# On_Board_Computer.net
KiCad netlist of a schematic drawn in EAGLE
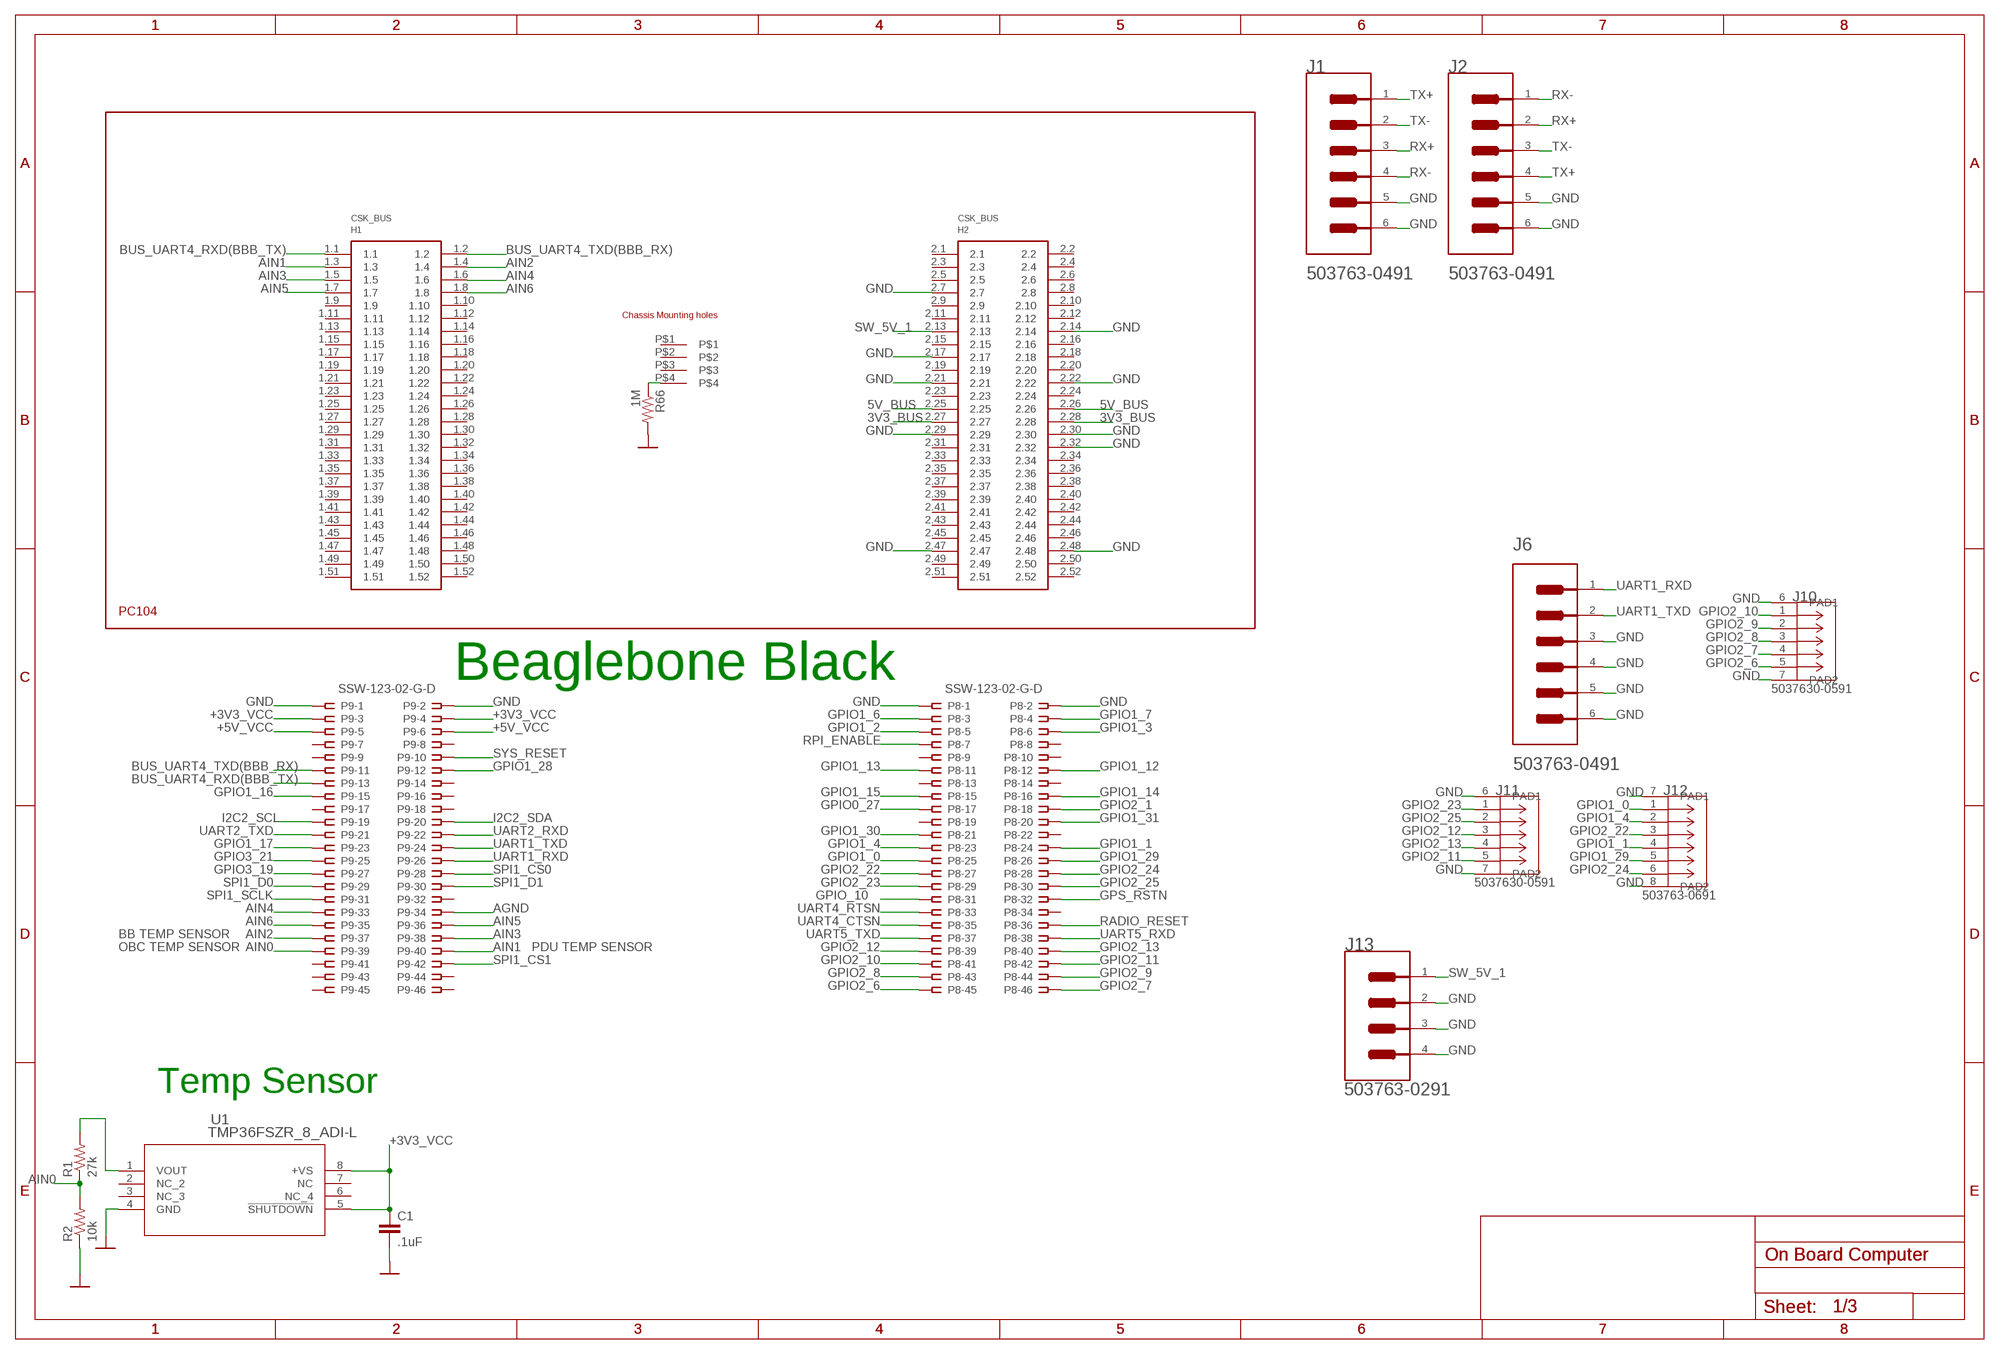
[diagram p0: schematic, sheet 1]
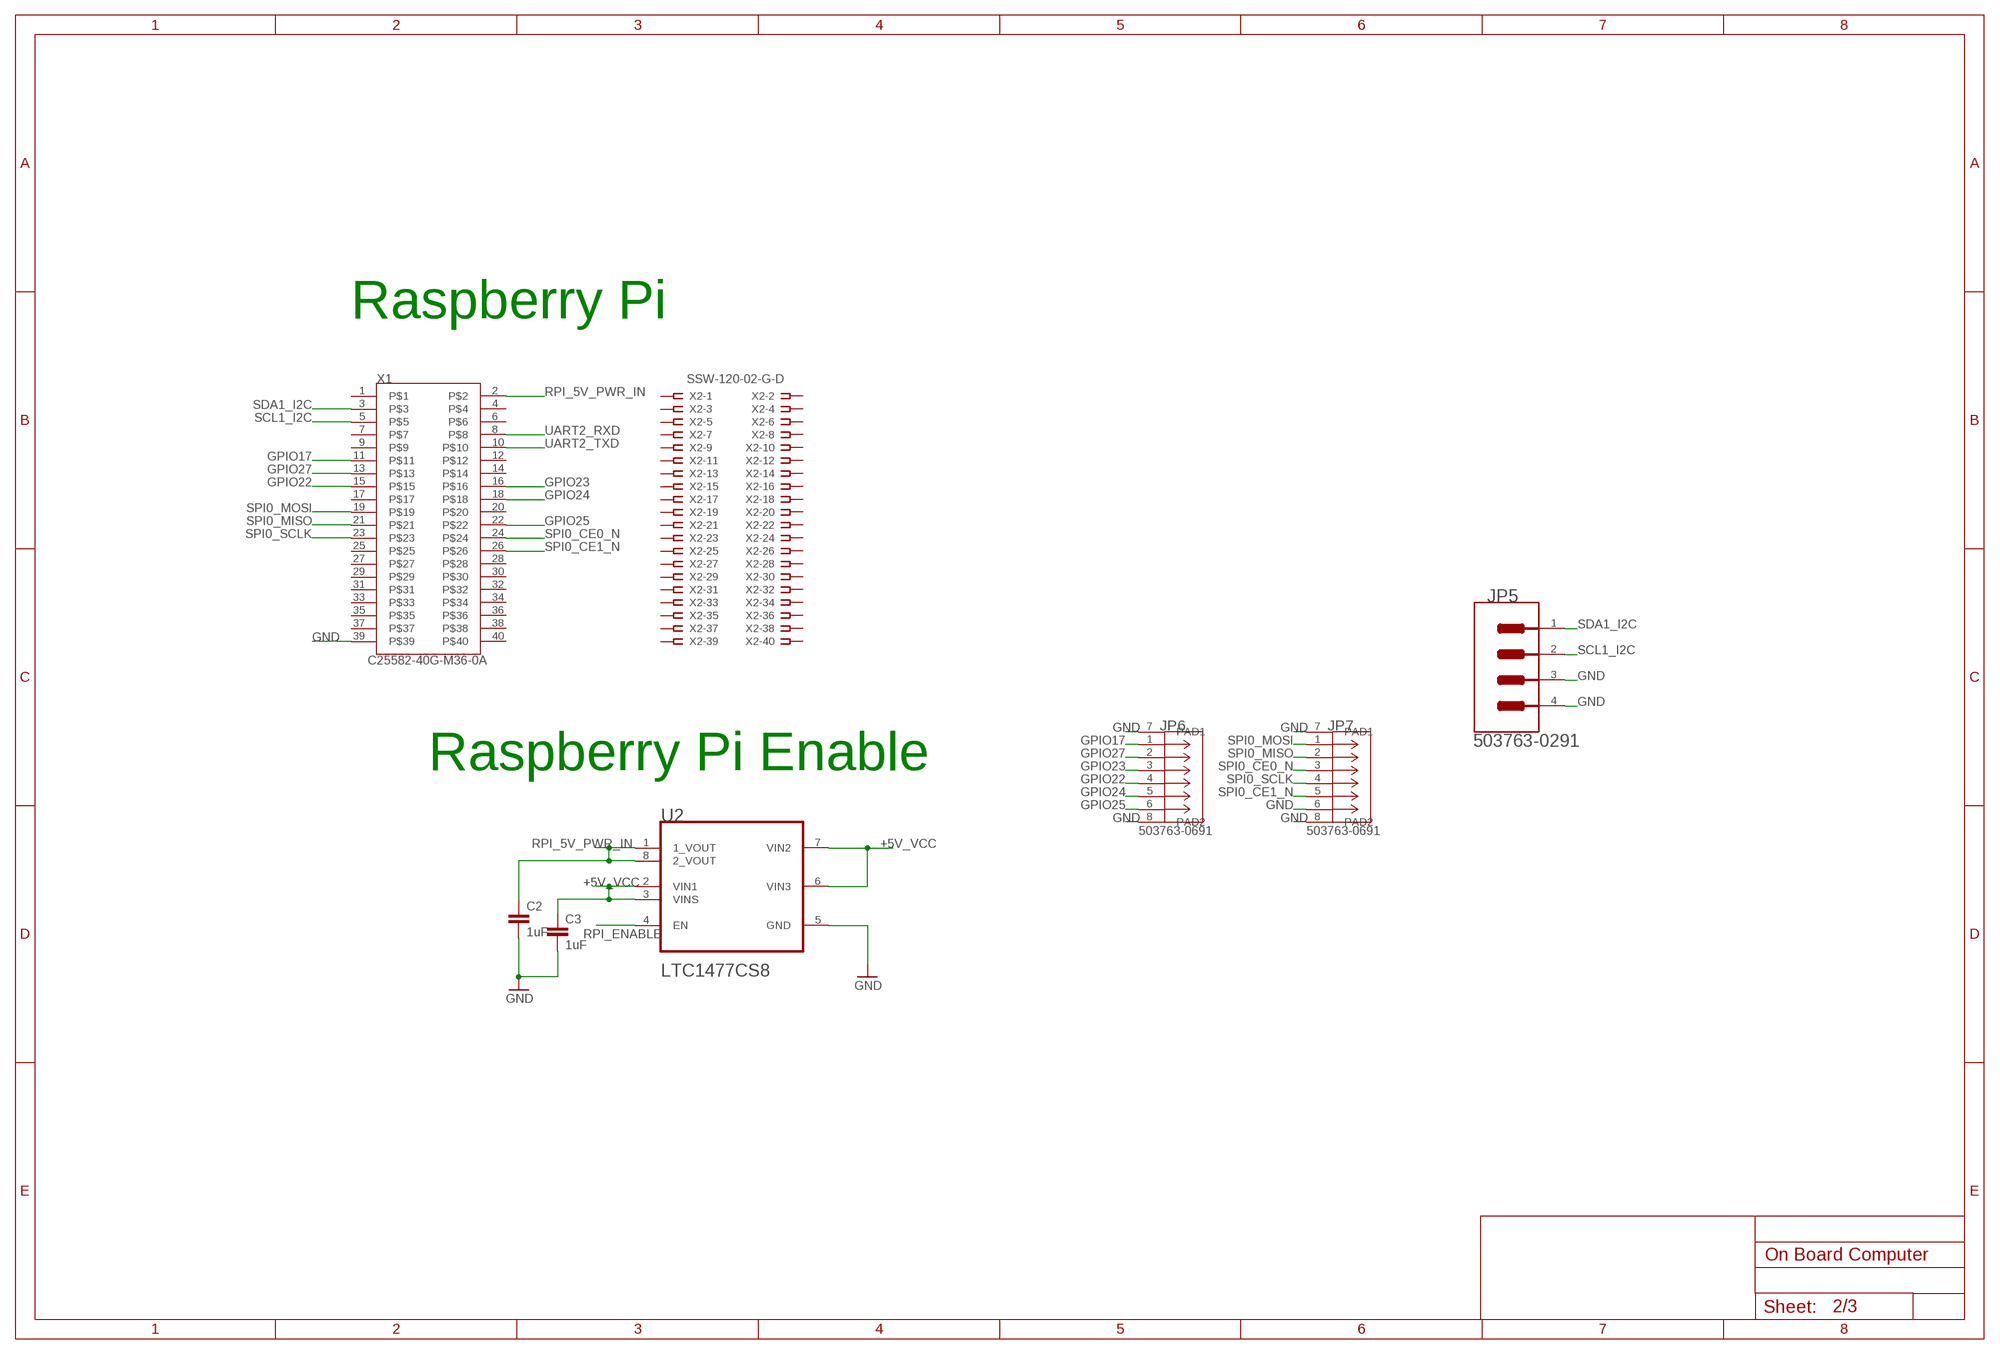
[diagram p1: schematic, sheet 2]
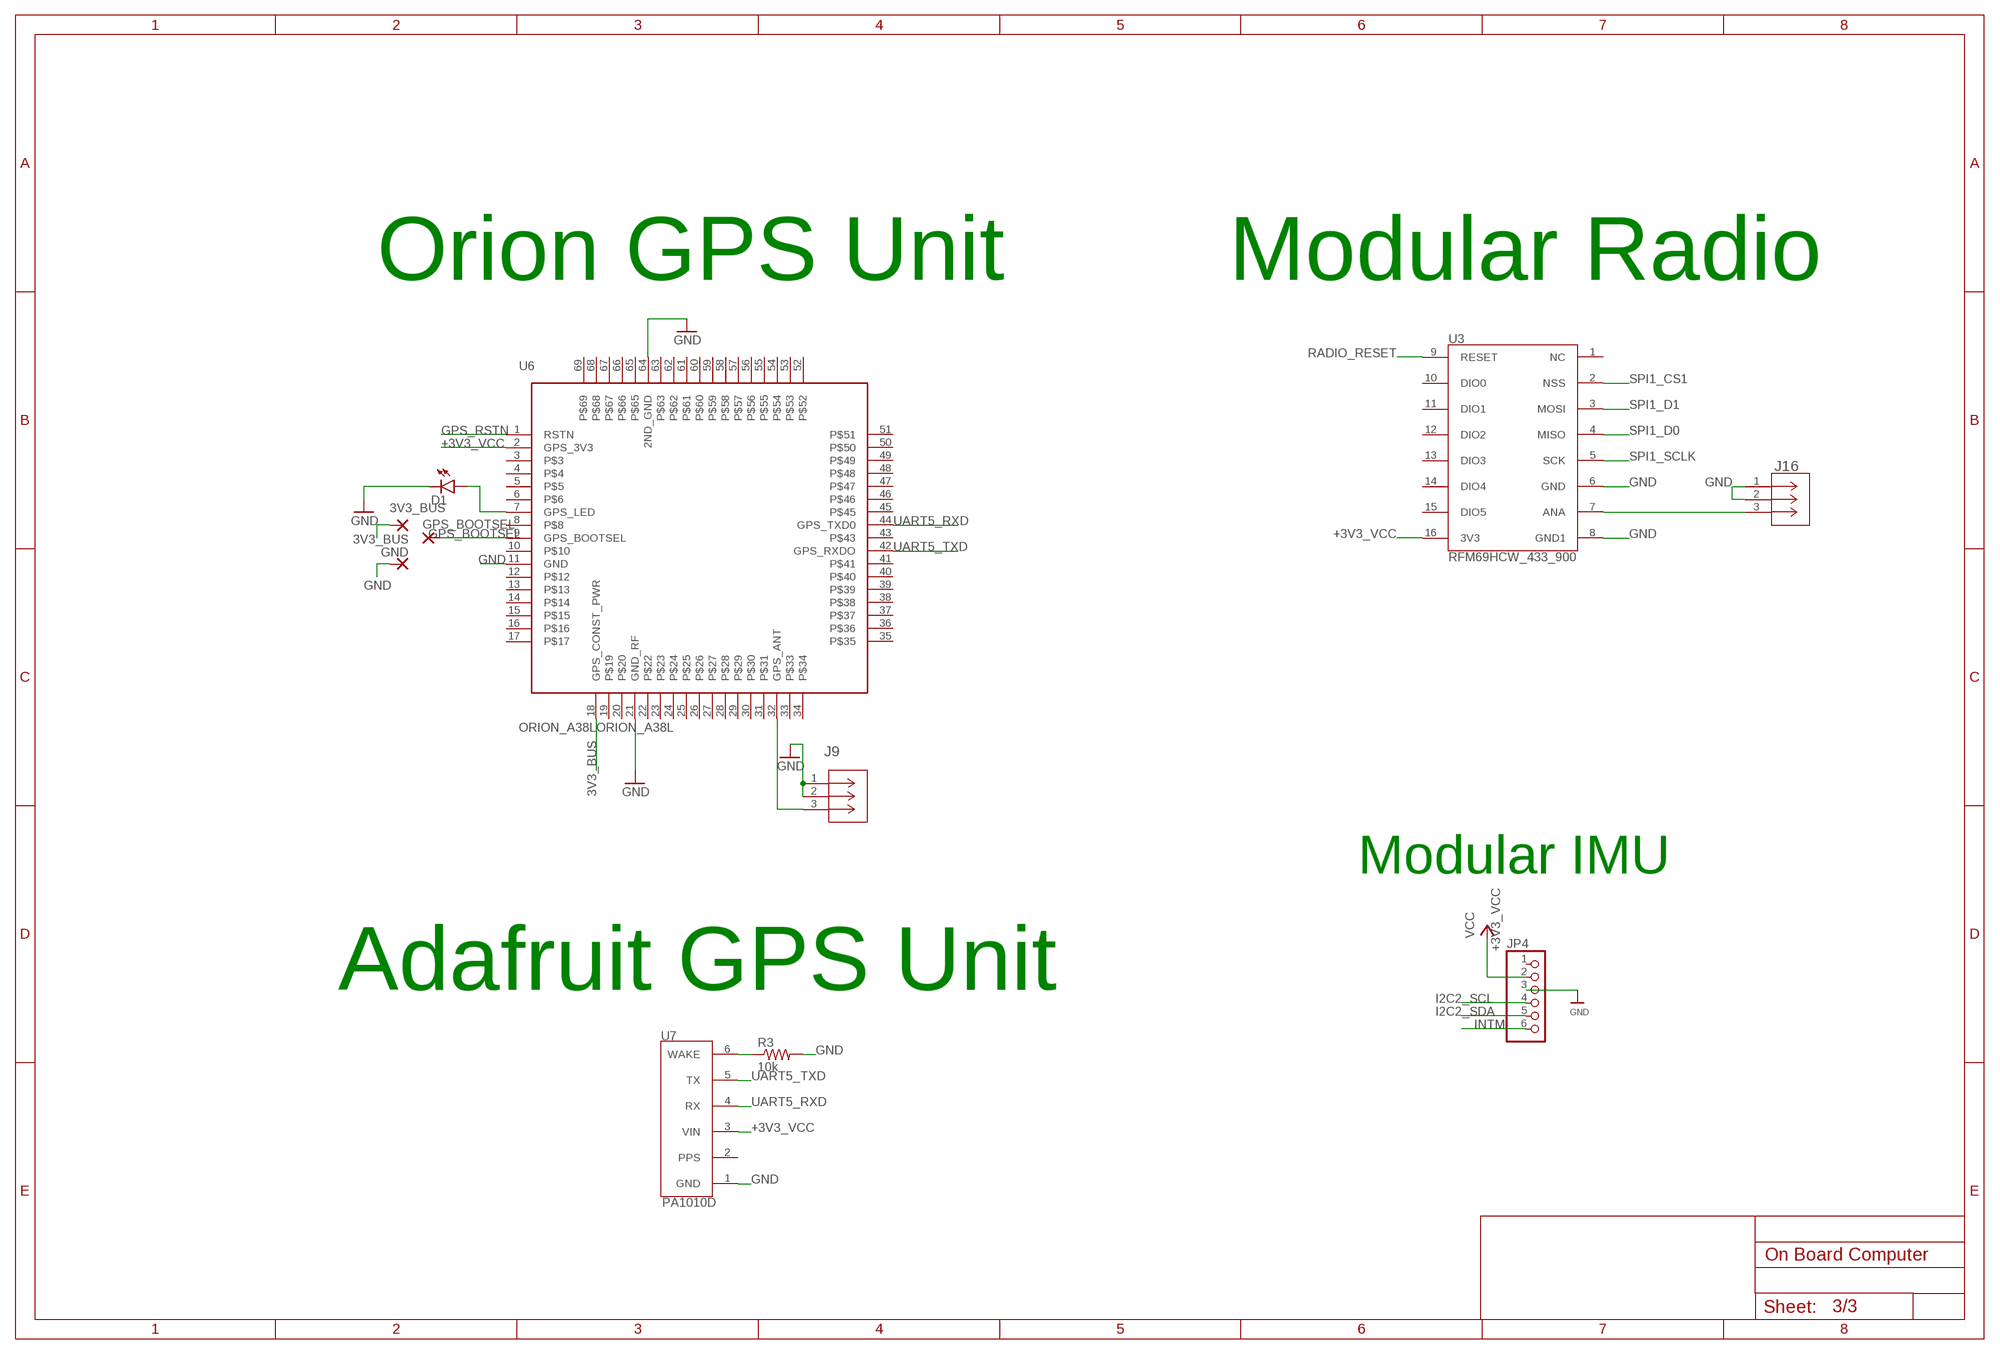
[diagram p2: schematic, sheet 3]

(export (version "E")
  (design (tool "Eeschema 10.0.6"))
  (components
    (comp (ref "3V3_BUS")
      (value "1,6/0,9")
      (footprint "eagle-import:1,6_0,9")
      (libsource (lib "eagle-import") (part "1,6/0,9"))
    )
    (comp (ref "D1")
      (value "LEDCHIP-LED0603")
      (footprint "eagle-import:CHIP-LED0603")
      (libsource (lib "eagle-import") (part "LEDCHIP-LED0603"))
    )
    (comp (ref "GND")
      (value "GND")
      (footprint "eagle-import:1,6_0,9")
      (libsource (lib "eagle-import") (part "1,6/0,9"))
    )
    (comp (ref "GPS_BOOTSEL")
      (value "1,6/0,9")
      (footprint "eagle-import:1,6_0,9")
      (libsource (lib "eagle-import") (part "1,6/0,9"))
    )
    (comp (ref "J9")
      (value "U.FL-R-SMT-1(01)")
      (footprint "eagle-import:CONN_-SMT-1(01)")
      (fields (field (name "COPYRIGHT") "Copyright (C) 2018 Accelerated Designs. All rights reserved"))
      (libsource (lib "eagle-import") (part "U.FL-R-SMT-1(01)"))
    )
    (comp (ref "J16")
      (value "U.FL-R-SMT-1(01)")
      (footprint "eagle-import:CONN_-SMT-1(01)")
      (fields (field (name "COPYRIGHT") "Copyright (C) 2018 Accelerated Designs. All rights reserved"))
      (libsource (lib "eagle-import") (part "U.FL-R-SMT-1(01)"))
    )
    (comp (ref "JP4")
      (value "HEADER-1X670MIL")
      (footprint "eagle-import:1X06_ROUND_70")
      (libsource (lib "eagle-import") (part "HEADER-1X670MIL"))
    )
    (comp (ref "R3")
      (value "10k")
      (footprint "eagle-import:0805")
      (libsource (lib "eagle-import") (part "RESISTOR0805-RES"))
    )
    (comp (ref "U3")
      (value "RFM69HCW_433_900")
      (footprint "eagle-import:RFM69HCW_433")
      (libsource (lib "eagle-import") (part "RFM69HCW_433_900"))
    )
    (comp (ref "U6")
      (value "ORION_A38LORION_A38L")
      (footprint "eagle-import:ORION_A38L")
      (libsource (lib "eagle-import") (part "ORION_A38LORION_A38L"))
    )
    (comp (ref "U7")
      (value "PA1010D")
      (footprint "eagle-import:PA1010D")
      (libsource (lib "eagle-import") (part "PA1010D"))
    )
    (comp (ref "C1")
      (value ".1uF")
      (footprint "eagle-import:0805")
      (libsource (lib "eagle-import") (part "CAP0805"))
    )
    (comp (ref "H1")
      (value "PC104_WCONN")
      (footprint "eagle-import:PC104_WCONN")
      (libsource (lib "eagle-import") (part "PC104_WCONN"))
    )
    (comp (ref "J1")
      (value "MOLEX_503763-0491MOLEX_503763-0491_0_0")
      (footprint "eagle-import:MOLEX_503763-0491_0")
      (fields
        (field (name "DIGIKEY_PART_NUMBER") "WM10655CT-ND")
        (field (name "MF") "Molex")
        (field (name "MOUSER_PART_NUMBER") "538-503763-0491")
      )
      (libsource (lib "eagle-import") (part "MOLEX_503763-0491MOLEX_503763-0491_0_0"))
    )
    (comp (ref "J2")
      (value "MOLEX_503763-0491MOLEX_503763-0491_0_0")
      (footprint "eagle-import:MOLEX_503763-0491_0")
      (fields
        (field (name "DIGIKEY_PART_NUMBER") "WM10655CT-ND")
        (field (name "MF") "Molex")
        (field (name "MOUSER_PART_NUMBER") "538-503763-0491")
      )
      (libsource (lib "eagle-import") (part "MOLEX_503763-0491MOLEX_503763-0491_0_0"))
    )
    (comp (ref "J6")
      (value "MOLEX_503763-0491MOLEX_503763-0491_0_0")
      (footprint "eagle-import:MOLEX_503763-0491_0")
      (fields
        (field (name "DIGIKEY_PART_NUMBER") "WM10655CT-ND")
        (field (name "MF") "Molex")
        (field (name "MOUSER_PART_NUMBER") "538-503763-0491")
      )
      (libsource (lib "eagle-import") (part "MOLEX_503763-0491MOLEX_503763-0491_0_0"))
    )
    (comp (ref "J10")
      (value "503763-0591")
      (footprint "eagle-import:CONN_5037630591_MOL")
      (fields (field (name "COPYRIGHT") "Copyright (C) 2018 Accelerated Designs. All rights reserved"))
      (libsource (lib "eagle-import") (part "503763-0591"))
    )
    (comp (ref "J11")
      (value "503763-0591")
      (footprint "eagle-import:CONN_5037630591_MOL")
      (fields (field (name "COPYRIGHT") "Copyright (C) 2018 Accelerated Designs. All rights reserved"))
      (libsource (lib "eagle-import") (part "503763-0591"))
    )
    (comp (ref "J12")
      (value "503763-0691")
      (footprint "eagle-import:CONN_503763-0691_MOL")
      (fields (field (name "COPYRIGHT") "Copyright (C) 2018 Accelerated Designs. All rights reserved"))
      (libsource (lib "eagle-import") (part "503763-0691"))
    )
    (comp (ref "J13")
      (value "MOLEX_503763-0291MOLEX_503763-0291_0_0")
      (footprint "eagle-import:MOLEX_503763-0291_0")
      (fields
        (field (name "DIGIKEY_PART_NUMBER") "WM10654CT-ND")
        (field (name "MF") "Molex")
        (field (name "MOUSER_PART_NUMBER") "538-503763-0291")
      )
      (libsource (lib "eagle-import") (part "MOLEX_503763-0291MOLEX_503763-0291_0_0"))
    )
    (comp (ref "P8")
      (value "SSW-123-02-G-D")
      (footprint "eagle-import:SSW-123-02-G-D")
      (fields (field (name "MF") "Samtec Inc."))
      (libsource (lib "eagle-import") (part "SSW-123-02-G-D"))
    )
    (comp (ref "P9")
      (value "SSW-123-02-G-D")
      (footprint "eagle-import:SSW-123-02-G-D")
      (fields (field (name "MF") "Samtec Inc."))
      (libsource (lib "eagle-import") (part "SSW-123-02-G-D"))
    )
    (comp (ref "R1")
      (value "27k")
      (footprint "eagle-import:0805")
      (libsource (lib "eagle-import") (part "RESISTOR0805-RES"))
    )
    (comp (ref "R2")
      (value "10k")
      (footprint "eagle-import:0805")
      (libsource (lib "eagle-import") (part "RESISTOR0805-RES"))
    )
    (comp (ref "R66")
      (value "1M")
      (footprint "eagle-import:0805")
      (libsource (lib "eagle-import") (part "RESISTOR0805-RES"))
    )
    (comp (ref "U1")
      (value "TMP36FSZR_8_ADI-L")
      (footprint "eagle-import:R_8_ADI-L")
      (fields
        (field (name "MANUFACTURER_PART_NUMBER") "TMP36FSZ")
        (field (name "COPYRIGHT") "Copyright (C) 2021 Ultra Librarian. All rights reserved.")
      )
      (libsource (lib "eagle-import") (part "TMP36FSZR_8_ADI-L"))
    )
    (comp (ref "C2")
      (value "1uF")
      (footprint "eagle-import:0805")
      (libsource (lib "eagle-import") (part "CAP0805"))
    )
    (comp (ref "C3")
      (value "1uF")
      (footprint "eagle-import:0805")
      (libsource (lib "eagle-import") (part "CAP0805"))
    )
    (comp (ref "JP5")
      (value "MOLEX_503763-0291MOLEX_503763-0291_0_0")
      (footprint "eagle-import:MOLEX_503763-0291_0")
      (fields
        (field (name "DIGIKEY_PART_NUMBER") "WM10654CT-ND")
        (field (name "MF") "Molex")
        (field (name "MOUSER_PART_NUMBER") "538-503763-0291")
      )
      (libsource (lib "eagle-import") (part "MOLEX_503763-0291MOLEX_503763-0291_0_0"))
    )
    (comp (ref "JP6")
      (value "503763-0691")
      (footprint "eagle-import:CONN_503763-0691_MOL")
      (fields (field (name "COPYRIGHT") "Copyright (C) 2018 Accelerated Designs. All rights reserved"))
      (libsource (lib "eagle-import") (part "503763-0691"))
    )
    (comp (ref "JP7")
      (value "503763-0691")
      (footprint "eagle-import:CONN_503763-0691_MOL")
      (fields (field (name "COPYRIGHT") "Copyright (C) 2018 Accelerated Designs. All rights reserved"))
      (libsource (lib "eagle-import") (part "503763-0691"))
    )
    (comp (ref "U2")
      (value "LTC1477CS8LINEAR_TECHNOLOGY_LTC1477CS8_0_2")
      (footprint "eagle-import:LINEAR_TECHNOLOGY_LTC1477CS8_2")
      (fields (field (name "MF") "Linear Technology") (field (name "MPN") "LTC1477CS8"))
      (libsource (lib "eagle-import") (part "LTC1477CS8LINEAR_TECHNOLOGY_LTC1477CS8_0_2"))
    )
    (comp (ref "X1")
      (value "C25582-40G-M36-0A")
      (footprint "eagle-import:ADAFRUIT_C25582-40G-M36-0A_0")
      (libsource (lib "eagle-import") (part "C25582-40G-M36-0A"))
    )
    (comp (ref "X2")
      (value "SSW-120-02-G-D")
      (footprint "eagle-import:SSW-120-02-G-D")
      (fields (field (name "MF") "Samtec Inc."))
      (libsource (lib "eagle-import") (part "SSW-120-02-G-D"))
    )
  )
  (nets
    (net (code "1") (name "+3V3_VCC") (class "Default")
      (node (ref "C1") (pin "1") (pinfunction "1_1") (pintype "passive"))
      (node (ref "JP4") (pin "2") (pinfunction "2_2") (pintype "passive"))
      (node (ref "P9") (pin "3") (pinfunction "1_3") (pintype "passive"))
      (node (ref "P9") (pin "4") (pinfunction "1_4") (pintype "passive"))
      (node (ref "U1") (pin "5") (pinfunction "~{SHUTDOWN}_5") (pintype "passive"))
      (node (ref "U1") (pin "8") (pinfunction "+VS_8") (pintype "power_in"))
      (node (ref "U3") (pin "16") (pinfunction "3V3_16") (pintype "bidirectional"))
      (node (ref "U6") (pin "2") (pinfunction "GPS_3V3_2") (pintype "bidirectional"))
      (node (ref "U7") (pin "3") (pinfunction "VIN_3") (pintype "bidirectional"))
    )
    (net (code "2") (name "+5V_VCC") (class "Default")
      (node (ref "C3") (pin "1") (pinfunction "1_1") (pintype "passive"))
      (node (ref "P9") (pin "5") (pinfunction "1_5") (pintype "passive"))
      (node (ref "P9") (pin "6") (pinfunction "1_6") (pintype "passive"))
      (node (ref "U2") (pin "2") (pinfunction "VIN1_2") (pintype "power_in"))
      (node (ref "U2") (pin "3") (pinfunction "VINS_3") (pintype "power_in"))
      (node (ref "U2") (pin "6") (pinfunction "VIN3_6") (pintype "power_in"))
      (node (ref "U2") (pin "7") (pinfunction "VIN2_7") (pintype "power_in"))
    )
    (net (code "3") (name "3V3_BUS") (class "Default")
      (node (ref "3V3_BUS") (pin "1") (pinfunction "P_1") (pintype "passive"))
      (node (ref "H1") (pin "2.27") (pinfunction "2.27_2.27") (pintype "bidirectional"))
      (node (ref "H1") (pin "2.28") (pinfunction "2.28_2.28") (pintype "bidirectional"))
      (node (ref "U6") (pin "18") (pinfunction "GPS_CONST_PWR_18") (pintype "bidirectional"))
    )
    (net (code "4") (name "5V_BUS") (class "Default")
      (node (ref "H1") (pin "2.25") (pinfunction "2.25_2.25") (pintype "bidirectional"))
      (node (ref "H1") (pin "2.26") (pinfunction "2.26_2.26") (pintype "bidirectional"))
    )
    (net (code "5") (name "AGND") (class "Default")
      (node (ref "P9") (pin "34") (pinfunction "1_34") (pintype "passive"))
    )
    (net (code "6") (name "AIN0") (class "Default")
      (node (ref "P9") (pin "39") (pinfunction "1_39") (pintype "passive"))
      (node (ref "R1") (pin "1") (pinfunction "1_1") (pintype "passive"))
      (node (ref "R2") (pin "2") (pinfunction "2_2") (pintype "passive"))
    )
    (net (code "7") (name "AIN1") (class "Default")
      (node (ref "H1") (pin "1.3") (pinfunction "1.3_1.3") (pintype "bidirectional"))
      (node (ref "P9") (pin "40") (pinfunction "1_40") (pintype "passive"))
    )
    (net (code "8") (name "AIN2") (class "Default")
      (node (ref "H1") (pin "1.4") (pinfunction "1.4_1.4") (pintype "bidirectional"))
      (node (ref "P9") (pin "37") (pinfunction "1_37") (pintype "passive"))
    )
    (net (code "9") (name "AIN3") (class "Default")
      (node (ref "H1") (pin "1.5") (pinfunction "1.5_1.5") (pintype "bidirectional"))
      (node (ref "P9") (pin "38") (pinfunction "1_38") (pintype "passive"))
    )
    (net (code "10") (name "AIN4") (class "Default")
      (node (ref "H1") (pin "1.6") (pinfunction "1.6_1.6") (pintype "bidirectional"))
      (node (ref "P9") (pin "33") (pinfunction "1_33") (pintype "passive"))
    )
    (net (code "11") (name "AIN5") (class "Default")
      (node (ref "H1") (pin "1.7") (pinfunction "1.7_1.7") (pintype "bidirectional"))
      (node (ref "P9") (pin "36") (pinfunction "1_36") (pintype "passive"))
    )
    (net (code "12") (name "AIN6") (class "Default")
      (node (ref "H1") (pin "1.8") (pinfunction "1.8_1.8") (pintype "bidirectional"))
      (node (ref "P9") (pin "35") (pinfunction "1_35") (pintype "passive"))
    )
    (net (code "13") (name "BUS_UART4_RXD(BBB_TX)") (class "Default")
      (node (ref "H1") (pin "1.1") (pinfunction "1.1_1.1") (pintype "bidirectional"))
      (node (ref "P9") (pin "13") (pinfunction "1_13") (pintype "passive"))
    )
    (net (code "14") (name "BUS_UART4_TXD(BBB_RX)") (class "Default")
      (node (ref "H1") (pin "1.2") (pinfunction "1.2_1.2") (pintype "bidirectional"))
      (node (ref "P9") (pin "11") (pinfunction "1_11") (pintype "passive"))
    )
    (net (code "15") (name "GND") (class "Default")
      (node (ref "C1") (pin "2") (pinfunction "2_2") (pintype "passive"))
      (node (ref "C2") (pin "2") (pinfunction "2_2") (pintype "passive"))
      (node (ref "C3") (pin "2") (pinfunction "2_2") (pintype "passive"))
      (node (ref "D1") (pin "C") (pinfunction "C_C") (pintype "passive"))
      (node (ref "GND") (pin "1") (pinfunction "P_1") (pintype "passive"))
      (node (ref "H1") (pin "2.14") (pinfunction "2.14_2.14") (pintype "bidirectional"))
      (node (ref "H1") (pin "2.17") (pinfunction "2.17_2.17") (pintype "bidirectional"))
      (node (ref "H1") (pin "2.21") (pinfunction "2.21_2.21") (pintype "bidirectional"))
      (node (ref "H1") (pin "2.22") (pinfunction "2.22_2.22") (pintype "bidirectional"))
      (node (ref "H1") (pin "2.29") (pinfunction "2.29_2.29") (pintype "bidirectional"))
      (node (ref "H1") (pin "2.30") (pinfunction "2.30_2.30") (pintype "bidirectional"))
      (node (ref "H1") (pin "2.32") (pinfunction "2.32_2.32") (pintype "bidirectional"))
      (node (ref "H1") (pin "2.47") (pinfunction "2.47_2.47") (pintype "bidirectional"))
      (node (ref "H1") (pin "2.48") (pinfunction "2.48_2.48") (pintype "bidirectional"))
      (node (ref "H1") (pin "2.7") (pinfunction "2.7_2.7") (pintype "bidirectional"))
      (node (ref "J1") (pin "5") (pinfunction "MNT_1_5") (pintype "passive"))
      (node (ref "J1") (pin "6") (pinfunction "MNT_2_6") (pintype "passive"))
      (node (ref "J10") (pin "6") (pinfunction "PAD1_6") (pintype "bidirectional"))
      (node (ref "J10") (pin "7") (pinfunction "PAD2_7") (pintype "bidirectional"))
      (node (ref "J11") (pin "6") (pinfunction "PAD1_6") (pintype "bidirectional"))
      (node (ref "J11") (pin "7") (pinfunction "PAD2_7") (pintype "bidirectional"))
      (node (ref "J12") (pin "7") (pinfunction "PAD1_7") (pintype "bidirectional"))
      (node (ref "J12") (pin "8") (pinfunction "PAD2_8") (pintype "bidirectional"))
      (node (ref "J13") (pin "2") (pinfunction "2_2") (pintype "bidirectional"))
      (node (ref "J13") (pin "3") (pinfunction "MNT_1_3") (pintype "bidirectional"))
      (node (ref "J13") (pin "4") (pinfunction "MNT_2_4") (pintype "bidirectional"))
      (node (ref "J16") (pin "1") (pinfunction "1_1") (pintype "passive"))
      (node (ref "J16") (pin "2") (pinfunction "2_2") (pintype "passive"))
      (node (ref "J2") (pin "5") (pinfunction "MNT_1_5") (pintype "passive"))
      (node (ref "J2") (pin "6") (pinfunction "MNT_2_6") (pintype "passive"))
      (node (ref "J6") (pin "3") (pinfunction "3_3") (pintype "passive"))
      (node (ref "J6") (pin "4") (pinfunction "4_4") (pintype "passive"))
      (node (ref "J6") (pin "5") (pinfunction "MNT_1_5") (pintype "passive"))
      (node (ref "J6") (pin "6") (pinfunction "MNT_2_6") (pintype "passive"))
      (node (ref "J9") (pin "1") (pinfunction "1_1") (pintype "passive"))
      (node (ref "J9") (pin "2") (pinfunction "2_2") (pintype "passive"))
      (node (ref "JP4") (pin "3") (pinfunction "3_3") (pintype "passive"))
      (node (ref "JP5") (pin "3") (pinfunction "MNT_1_3") (pintype "bidirectional"))
      (node (ref "JP5") (pin "4") (pinfunction "MNT_2_4") (pintype "bidirectional"))
      (node (ref "JP6") (pin "7") (pinfunction "PAD1_7") (pintype "bidirectional"))
      (node (ref "JP6") (pin "8") (pinfunction "PAD2_8") (pintype "bidirectional"))
      (node (ref "JP7") (pin "6") (pinfunction "6_6") (pintype "passive"))
      (node (ref "JP7") (pin "7") (pinfunction "PAD1_7") (pintype "bidirectional"))
      (node (ref "JP7") (pin "8") (pinfunction "PAD2_8") (pintype "bidirectional"))
      (node (ref "P8") (pin "1") (pinfunction "1_1") (pintype "passive"))
      (node (ref "P8") (pin "2") (pinfunction "1_2") (pintype "passive"))
      (node (ref "P9") (pin "1") (pinfunction "1_1") (pintype "passive"))
      (node (ref "P9") (pin "2") (pinfunction "1_2") (pintype "passive"))
      (node (ref "R2") (pin "1") (pinfunction "1_1") (pintype "passive"))
      (node (ref "R3") (pin "2") (pinfunction "2_2") (pintype "passive"))
      (node (ref "R66") (pin "2") (pinfunction "2_2") (pintype "passive"))
      (node (ref "U1") (pin "4") (pinfunction "GND_4") (pintype "passive"))
      (node (ref "U2") (pin "5") (pinfunction "GND_5") (pintype "power_in"))
      (node (ref "U3") (pin "6") (pinfunction "GND_6") (pintype "bidirectional"))
      (node (ref "U3") (pin "8") (pinfunction "GND1_8") (pintype "bidirectional"))
      (node (ref "U6") (pin "11") (pinfunction "GND_11") (pintype "bidirectional"))
      (node (ref "U6") (pin "21") (pinfunction "GND_RF_21") (pintype "bidirectional"))
      (node (ref "U6") (pin "64") (pinfunction "2ND_GND_64") (pintype "bidirectional"))
      (node (ref "U7") (pin "1") (pinfunction "GND_1") (pintype "bidirectional"))
      (node (ref "X1") (pin "39") (pinfunction "P$39_39") (pintype "bidirectional"))
    )
    (net (code "16") (name "GPIO0_27") (class "Default")
      (node (ref "P8") (pin "17") (pinfunction "1_17") (pintype "passive"))
    )
    (net (code "17") (name "GPIO1_0") (class "Default")
      (node (ref "J12") (pin "1") (pinfunction "1_1") (pintype "passive"))
      (node (ref "P8") (pin "25") (pinfunction "1_25") (pintype "passive"))
    )
    (net (code "18") (name "GPIO1_1") (class "Default")
      (node (ref "J12") (pin "4") (pinfunction "4_4") (pintype "passive"))
      (node (ref "P8") (pin "24") (pinfunction "1_24") (pintype "passive"))
    )
    (net (code "19") (name "GPIO1_2") (class "Default")
      (node (ref "P8") (pin "5") (pinfunction "1_5") (pintype "passive"))
    )
    (net (code "20") (name "GPIO1_3") (class "Default")
      (node (ref "P8") (pin "6") (pinfunction "1_6") (pintype "passive"))
    )
    (net (code "21") (name "GPIO1_4") (class "Default")
      (node (ref "J12") (pin "2") (pinfunction "2_2") (pintype "passive"))
      (node (ref "P8") (pin "23") (pinfunction "1_23") (pintype "passive"))
    )
    (net (code "22") (name "GPIO1_6") (class "Default")
      (node (ref "P8") (pin "3") (pinfunction "1_3") (pintype "passive"))
    )
    (net (code "23") (name "GPIO1_7") (class "Default")
      (node (ref "P8") (pin "4") (pinfunction "1_4") (pintype "passive"))
    )
    (net (code "24") (name "GPIO1_12") (class "Default")
      (node (ref "P8") (pin "12") (pinfunction "1_12") (pintype "passive"))
    )
    (net (code "25") (name "GPIO1_13") (class "Default")
      (node (ref "P8") (pin "11") (pinfunction "1_11") (pintype "passive"))
    )
    (net (code "26") (name "GPIO1_14") (class "Default")
      (node (ref "P8") (pin "16") (pinfunction "1_16") (pintype "passive"))
    )
    (net (code "27") (name "GPIO1_15") (class "Default")
      (node (ref "P8") (pin "15") (pinfunction "1_15") (pintype "passive"))
    )
    (net (code "28") (name "GPIO1_16") (class "Default")
      (node (ref "P9") (pin "15") (pinfunction "1_15") (pintype "passive"))
    )
    (net (code "29") (name "GPIO1_17") (class "Default")
      (node (ref "P9") (pin "23") (pinfunction "1_23") (pintype "passive"))
    )
    (net (code "30") (name "GPIO1_28") (class "Default")
      (node (ref "P9") (pin "12") (pinfunction "1_12") (pintype "passive"))
    )
    (net (code "31") (name "GPIO1_29") (class "Default")
      (node (ref "J12") (pin "5") (pinfunction "5_5") (pintype "passive"))
      (node (ref "P8") (pin "26") (pinfunction "1_26") (pintype "passive"))
    )
    (net (code "32") (name "GPIO1_30") (class "Default")
      (node (ref "P8") (pin "21") (pinfunction "1_21") (pintype "passive"))
    )
    (net (code "33") (name "GPIO1_31") (class "Default")
      (node (ref "P8") (pin "20") (pinfunction "1_20") (pintype "passive"))
    )
    (net (code "34") (name "GPIO2_1") (class "Default")
      (node (ref "P8") (pin "18") (pinfunction "1_18") (pintype "passive"))
    )
    (net (code "35") (name "GPIO2_6") (class "Default")
      (node (ref "J10") (pin "5") (pinfunction "5_5") (pintype "passive"))
      (node (ref "P8") (pin "45") (pinfunction "1_45") (pintype "passive"))
    )
    (net (code "36") (name "GPIO2_7") (class "Default")
      (node (ref "J10") (pin "4") (pinfunction "4_4") (pintype "passive"))
      (node (ref "P8") (pin "46") (pinfunction "1_46") (pintype "passive"))
    )
    (net (code "37") (name "GPIO2_8") (class "Default")
      (node (ref "J10") (pin "3") (pinfunction "3_3") (pintype "passive"))
      (node (ref "P8") (pin "43") (pinfunction "1_43") (pintype "passive"))
    )
    (net (code "38") (name "GPIO2_9") (class "Default")
      (node (ref "J10") (pin "2") (pinfunction "2_2") (pintype "passive"))
      (node (ref "P8") (pin "44") (pinfunction "1_44") (pintype "passive"))
    )
    (net (code "39") (name "GPIO2_10") (class "Default")
      (node (ref "J10") (pin "1") (pinfunction "1_1") (pintype "passive"))
      (node (ref "P8") (pin "41") (pinfunction "1_41") (pintype "passive"))
    )
    (net (code "40") (name "GPIO2_11") (class "Default")
      (node (ref "J11") (pin "5") (pinfunction "5_5") (pintype "passive"))
      (node (ref "P8") (pin "42") (pinfunction "1_42") (pintype "passive"))
    )
    (net (code "41") (name "GPIO2_12") (class "Default")
      (node (ref "J11") (pin "3") (pinfunction "3_3") (pintype "passive"))
      (node (ref "P8") (pin "39") (pinfunction "1_39") (pintype "passive"))
    )
    (net (code "42") (name "GPIO2_13") (class "Default")
      (node (ref "J11") (pin "4") (pinfunction "4_4") (pintype "passive"))
      (node (ref "P8") (pin "40") (pinfunction "1_40") (pintype "passive"))
    )
    (net (code "43") (name "GPIO2_22") (class "Default")
      (node (ref "J12") (pin "3") (pinfunction "3_3") (pintype "passive"))
      (node (ref "P8") (pin "27") (pinfunction "1_27") (pintype "passive"))
    )
    (net (code "44") (name "GPIO2_23") (class "Default")
      (node (ref "J11") (pin "1") (pinfunction "1_1") (pintype "passive"))
      (node (ref "P8") (pin "29") (pinfunction "1_29") (pintype "passive"))
    )
    (net (code "45") (name "GPIO2_24") (class "Default")
      (node (ref "J12") (pin "6") (pinfunction "6_6") (pintype "passive"))
      (node (ref "P8") (pin "28") (pinfunction "1_28") (pintype "passive"))
    )
    (net (code "46") (name "GPIO2_25") (class "Default")
      (node (ref "J11") (pin "2") (pinfunction "2_2") (pintype "passive"))
      (node (ref "P8") (pin "30") (pinfunction "1_30") (pintype "passive"))
    )
    (net (code "47") (name "GPIO3_19") (class "Default")
      (node (ref "P9") (pin "27") (pinfunction "1_27") (pintype "passive"))
    )
    (net (code "48") (name "GPIO3_21") (class "Default")
      (node (ref "P9") (pin "25") (pinfunction "1_25") (pintype "passive"))
    )
    (net (code "49") (name "GPIO17") (class "Default")
      (node (ref "JP6") (pin "1") (pinfunction "1_1") (pintype "passive"))
      (node (ref "X1") (pin "11") (pinfunction "P$11_11") (pintype "bidirectional"))
    )
    (net (code "50") (name "GPIO22") (class "Default")
      (node (ref "JP6") (pin "4") (pinfunction "4_4") (pintype "passive"))
      (node (ref "X1") (pin "15") (pinfunction "P$15_15") (pintype "bidirectional"))
    )
    (net (code "51") (name "GPIO23") (class "Default")
      (node (ref "JP6") (pin "3") (pinfunction "3_3") (pintype "passive"))
      (node (ref "X1") (pin "16") (pinfunction "P$16_16") (pintype "bidirectional"))
    )
    (net (code "52") (name "GPIO24") (class "Default")
      (node (ref "JP6") (pin "5") (pinfunction "5_5") (pintype "passive"))
      (node (ref "X1") (pin "18") (pinfunction "P$18_18") (pintype "bidirectional"))
    )
    (net (code "53") (name "GPIO25") (class "Default")
      (node (ref "JP6") (pin "6") (pinfunction "6_6") (pintype "passive"))
      (node (ref "X1") (pin "22") (pinfunction "P$22_22") (pintype "bidirectional"))
    )
    (net (code "54") (name "GPIO27") (class "Default")
      (node (ref "JP6") (pin "2") (pinfunction "2_2") (pintype "passive"))
      (node (ref "X1") (pin "13") (pinfunction "P$13_13") (pintype "bidirectional"))
    )
    (net (code "55") (name "GPIO_10") (class "Default")
      (node (ref "P8") (pin "31") (pinfunction "1_31") (pintype "passive"))
    )
    (net (code "56") (name "GPS_BOOTSEL") (class "Default")
      (node (ref "GPS_BOOTSEL") (pin "1") (pinfunction "P_1") (pintype "passive"))
      (node (ref "U6") (pin "9") (pinfunction "GPS_BOOTSEL_9") (pintype "bidirectional"))
    )
    (net (code "57") (name "GPS_RSTN") (class "Default")
      (node (ref "P8") (pin "32") (pinfunction "1_32") (pintype "passive"))
      (node (ref "U6") (pin "1") (pinfunction "RSTN_1") (pintype "bidirectional"))
    )
    (net (code "58") (name "I2C2_SCL") (class "Default")
      (node (ref "JP4") (pin "4") (pinfunction "4_4") (pintype "passive"))
      (node (ref "P9") (pin "19") (pinfunction "1_19") (pintype "passive"))
    )
    (net (code "59") (name "I2C2_SDA") (class "Default")
      (node (ref "JP4") (pin "5") (pinfunction "5_5") (pintype "passive"))
      (node (ref "P9") (pin "20") (pinfunction "1_20") (pintype "passive"))
    )
    (net (code "60") (name "INTM") (class "Default")
      (node (ref "JP4") (pin "6") (pinfunction "6_6") (pintype "passive"))
    )
    (net (code "61") (name "Net-(H1-PadP$4)") (class "Default")
      (node (ref "H1") (pin "P$4") (pinfunction "P$4_P$4") (pintype "bidirectional"))
      (node (ref "R66") (pin "1") (pinfunction "1_1") (pintype "passive"))
    )
    (net (code "62") (name "Net-(U1-VOUT)") (class "Default")
      (node (ref "R1") (pin "2") (pinfunction "2_2") (pintype "passive"))
      (node (ref "U1") (pin "1") (pinfunction "VOUT_1") (pintype "output"))
    )
    (net (code "63") (name "Net-(U3-ANA)") (class "Default")
      (node (ref "J16") (pin "3") (pinfunction "3_3") (pintype "passive"))
      (node (ref "U3") (pin "7") (pinfunction "ANA_7") (pintype "bidirectional"))
    )
    (net (code "64") (name "Net-(U6-GPS_ANT)") (class "Default")
      (node (ref "J9") (pin "3") (pinfunction "3_3") (pintype "passive"))
      (node (ref "U6") (pin "32") (pinfunction "GPS_ANT_32") (pintype "bidirectional"))
    )
    (net (code "65") (name "Net-(U6-GPS_LED)") (class "Default")
      (node (ref "D1") (pin "A") (pinfunction "A_A") (pintype "passive"))
      (node (ref "U6") (pin "7") (pinfunction "GPS_LED_7") (pintype "bidirectional"))
    )
    (net (code "66") (name "Net-(U7-WAKE)") (class "Default")
      (node (ref "R3") (pin "1") (pinfunction "1_1") (pintype "passive"))
      (node (ref "U7") (pin "6") (pinfunction "WAKE_6") (pintype "bidirectional"))
    )
    (net (code "67") (name "RADIO_RESET") (class "Default")
      (node (ref "P8") (pin "36") (pinfunction "1_36") (pintype "passive"))
      (node (ref "U3") (pin "9") (pinfunction "RESET_9") (pintype "bidirectional"))
    )
    (net (code "68") (name "RPI_5V_PWR_IN") (class "Default")
      (node (ref "C2") (pin "1") (pinfunction "1_1") (pintype "passive"))
      (node (ref "U2") (pin "1") (pinfunction "1_VOUT_1") (pintype "power_in"))
      (node (ref "U2") (pin "8") (pinfunction "2_VOUT_8") (pintype "power_in"))
      (node (ref "X1") (pin "2") (pinfunction "P$2_2") (pintype "bidirectional"))
    )
    (net (code "69") (name "RPI_ENABLE") (class "Default")
      (node (ref "P8") (pin "7") (pinfunction "1_7") (pintype "passive"))
      (node (ref "U2") (pin "4") (pinfunction "EN_4") (pintype "input"))
    )
    (net (code "70") (name "RX+") (class "Default")
      (node (ref "J1") (pin "3") (pinfunction "3_3") (pintype "passive"))
      (node (ref "J2") (pin "2") (pinfunction "2_2") (pintype "passive"))
    )
    (net (code "71") (name "RX-") (class "Default")
      (node (ref "J1") (pin "4") (pinfunction "4_4") (pintype "passive"))
      (node (ref "J2") (pin "1") (pinfunction "1_1") (pintype "passive"))
    )
    (net (code "72") (name "SCL1_I2C") (class "Default")
      (node (ref "JP5") (pin "2") (pinfunction "2_2") (pintype "bidirectional"))
      (node (ref "X1") (pin "5") (pinfunction "P$5_5") (pintype "bidirectional"))
    )
    (net (code "73") (name "SDA1_I2C") (class "Default")
      (node (ref "JP5") (pin "1") (pinfunction "1_1") (pintype "bidirectional"))
      (node (ref "X1") (pin "3") (pinfunction "P$3_3") (pintype "bidirectional"))
    )
    (net (code "74") (name "SPI0_CE0_N") (class "Default")
      (node (ref "JP7") (pin "3") (pinfunction "3_3") (pintype "passive"))
      (node (ref "X1") (pin "24") (pinfunction "P$24_24") (pintype "bidirectional"))
    )
    (net (code "75") (name "SPI0_CE1_N") (class "Default")
      (node (ref "JP7") (pin "5") (pinfunction "5_5") (pintype "passive"))
      (node (ref "X1") (pin "26") (pinfunction "P$26_26") (pintype "bidirectional"))
    )
    (net (code "76") (name "SPI0_MISO") (class "Default")
      (node (ref "JP7") (pin "2") (pinfunction "2_2") (pintype "passive"))
      (node (ref "X1") (pin "21") (pinfunction "P$21_21") (pintype "bidirectional"))
    )
    (net (code "77") (name "SPI0_MOSI") (class "Default")
      (node (ref "JP7") (pin "1") (pinfunction "1_1") (pintype "passive"))
      (node (ref "X1") (pin "19") (pinfunction "P$19_19") (pintype "bidirectional"))
    )
    (net (code "78") (name "SPI0_SCLK") (class "Default")
      (node (ref "JP7") (pin "4") (pinfunction "4_4") (pintype "passive"))
      (node (ref "X1") (pin "23") (pinfunction "P$23_23") (pintype "bidirectional"))
    )
    (net (code "79") (name "SPI1_CS0") (class "Default")
      (node (ref "P9") (pin "28") (pinfunction "1_28") (pintype "passive"))
    )
    (net (code "80") (name "SPI1_CS1") (class "Default")
      (node (ref "P9") (pin "42") (pinfunction "1_42") (pintype "passive"))
      (node (ref "U3") (pin "2") (pinfunction "NSS_2") (pintype "bidirectional"))
    )
    (net (code "81") (name "SPI1_D0") (class "Default")
      (node (ref "P9") (pin "29") (pinfunction "1_29") (pintype "passive"))
      (node (ref "U3") (pin "4") (pinfunction "MISO_4") (pintype "bidirectional"))
    )
    (net (code "82") (name "SPI1_D1") (class "Default")
      (node (ref "P9") (pin "30") (pinfunction "1_30") (pintype "passive"))
      (node (ref "U3") (pin "3") (pinfunction "MOSI_3") (pintype "bidirectional"))
    )
    (net (code "83") (name "SPI1_SCLK") (class "Default")
      (node (ref "P9") (pin "31") (pinfunction "1_31") (pintype "passive"))
      (node (ref "U3") (pin "5") (pinfunction "SCK_5") (pintype "bidirectional"))
    )
    (net (code "84") (name "SW_5V_1") (class "Default")
      (node (ref "H1") (pin "2.13") (pinfunction "2.13_2.13") (pintype "bidirectional"))
      (node (ref "J13") (pin "1") (pinfunction "1_1") (pintype "bidirectional"))
    )
    (net (code "85") (name "SYS_RESET") (class "Default")
      (node (ref "P9") (pin "10") (pinfunction "1_10") (pintype "passive"))
    )
    (net (code "86") (name "TX+") (class "Default")
      (node (ref "J1") (pin "1") (pinfunction "1_1") (pintype "passive"))
      (node (ref "J2") (pin "4") (pinfunction "4_4") (pintype "passive"))
    )
    (net (code "87") (name "TX-") (class "Default")
      (node (ref "J1") (pin "2") (pinfunction "2_2") (pintype "passive"))
      (node (ref "J2") (pin "3") (pinfunction "3_3") (pintype "passive"))
    )
    (net (code "88") (name "UART1_RXD") (class "Default")
      (node (ref "J6") (pin "1") (pinfunction "1_1") (pintype "passive"))
      (node (ref "P9") (pin "26") (pinfunction "1_26") (pintype "passive"))
    )
    (net (code "89") (name "UART1_TXD") (class "Default")
      (node (ref "J6") (pin "2") (pinfunction "2_2") (pintype "passive"))
      (node (ref "P9") (pin "24") (pinfunction "1_24") (pintype "passive"))
    )
    (net (code "90") (name "UART2_RXD") (class "Default")
      (node (ref "P9") (pin "22") (pinfunction "1_22") (pintype "passive"))
      (node (ref "X1") (pin "8") (pinfunction "P$8_8") (pintype "bidirectional"))
    )
    (net (code "91") (name "UART2_TXD") (class "Default")
      (node (ref "P9") (pin "21") (pinfunction "1_21") (pintype "passive"))
      (node (ref "X1") (pin "10") (pinfunction "P$10_10") (pintype "bidirectional"))
    )
    (net (code "92") (name "UART4_CTSN") (class "Default")
      (node (ref "P8") (pin "35") (pinfunction "1_35") (pintype "passive"))
    )
    (net (code "93") (name "UART4_RTSN") (class "Default")
      (node (ref "P8") (pin "33") (pinfunction "1_33") (pintype "passive"))
    )
    (net (code "94") (name "UART5_RXD") (class "Default")
      (node (ref "P8") (pin "38") (pinfunction "1_38") (pintype "passive"))
      (node (ref "U6") (pin "44") (pinfunction "GPS_TXD0_44") (pintype "output"))
      (node (ref "U7") (pin "4") (pinfunction "RX_4") (pintype "bidirectional"))
    )
    (net (code "95") (name "UART5_TXD") (class "Default")
      (node (ref "P8") (pin "37") (pinfunction "1_37") (pintype "passive"))
      (node (ref "U6") (pin "42") (pinfunction "GPS_RXDO_42") (pintype "input"))
      (node (ref "U7") (pin "5") (pinfunction "TX_5") (pintype "bidirectional"))
    )
    (net (code "96") (name "unconnected-(H1-Pad1.9)") (class "Default")
      (node (ref "H1") (pin "1.9") (pinfunction "1.9_1.9") (pintype "bidirectional"))
    )
    (net (code "97") (name "unconnected-(H1-Pad1.10)") (class "Default")
      (node (ref "H1") (pin "1.10") (pinfunction "1.10_1.10") (pintype "bidirectional"))
    )
    (net (code "98") (name "unconnected-(H1-Pad1.11)") (class "Default")
      (node (ref "H1") (pin "1.11") (pinfunction "1.11_1.11") (pintype "bidirectional"))
    )
    (net (code "99") (name "unconnected-(H1-Pad1.12)") (class "Default")
      (node (ref "H1") (pin "1.12") (pinfunction "1.12_1.12") (pintype "bidirectional"))
    )
    (net (code "100") (name "unconnected-(H1-Pad1.13)") (class "Default")
      (node (ref "H1") (pin "1.13") (pinfunction "1.13_1.13") (pintype "bidirectional"))
    )
    (net (code "101") (name "unconnected-(H1-Pad1.14)") (class "Default")
      (node (ref "H1") (pin "1.14") (pinfunction "1.14_1.14") (pintype "bidirectional"))
    )
    (net (code "102") (name "unconnected-(H1-Pad1.15)") (class "Default")
      (node (ref "H1") (pin "1.15") (pinfunction "1.15_1.15") (pintype "bidirectional"))
    )
    (net (code "103") (name "unconnected-(H1-Pad1.16)") (class "Default")
      (node (ref "H1") (pin "1.16") (pinfunction "1.16_1.16") (pintype "bidirectional"))
    )
    (net (code "104") (name "unconnected-(H1-Pad1.17)") (class "Default")
      (node (ref "H1") (pin "1.17") (pinfunction "1.17_1.17") (pintype "bidirectional"))
    )
    (net (code "105") (name "unconnected-(H1-Pad1.18)") (class "Default")
      (node (ref "H1") (pin "1.18") (pinfunction "1.18_1.18") (pintype "bidirectional"))
    )
    (net (code "106") (name "unconnected-(H1-Pad1.19)") (class "Default")
      (node (ref "H1") (pin "1.19") (pinfunction "1.19_1.19") (pintype "bidirectional"))
    )
    (net (code "107") (name "unconnected-(H1-Pad1.20)") (class "Default")
      (node (ref "H1") (pin "1.20") (pinfunction "1.20_1.20") (pintype "bidirectional"))
    )
    (net (code "108") (name "unconnected-(H1-Pad1.21)") (class "Default")
      (node (ref "H1") (pin "1.21") (pinfunction "1.21_1.21") (pintype "bidirectional"))
    )
    (net (code "109") (name "unconnected-(H1-Pad1.22)") (class "Default")
      (node (ref "H1") (pin "1.22") (pinfunction "1.22_1.22") (pintype "bidirectional"))
    )
    (net (code "110") (name "unconnected-(H1-Pad1.23)") (class "Default")
      (node (ref "H1") (pin "1.23") (pinfunction "1.23_1.23") (pintype "bidirectional"))
    )
    (net (code "111") (name "unconnected-(H1-Pad1.24)") (class "Default")
      (node (ref "H1") (pin "1.24") (pinfunction "1.24_1.24") (pintype "bidirectional"))
    )
    (net (code "112") (name "unconnected-(H1-Pad1.25)") (class "Default")
      (node (ref "H1") (pin "1.25") (pinfunction "1.25_1.25") (pintype "bidirectional"))
    )
    (net (code "113") (name "unconnected-(H1-Pad1.26)") (class "Default")
      (node (ref "H1") (pin "1.26") (pinfunction "1.26_1.26") (pintype "bidirectional"))
    )
    (net (code "114") (name "unconnected-(H1-Pad1.27)") (class "Default")
      (node (ref "H1") (pin "1.27") (pinfunction "1.27_1.27") (pintype "bidirectional"))
    )
    (net (code "115") (name "unconnected-(H1-Pad1.28)") (class "Default")
      (node (ref "H1") (pin "1.28") (pinfunction "1.28_1.28") (pintype "bidirectional"))
    )
    (net (code "116") (name "unconnected-(H1-Pad1.29)") (class "Default")
      (node (ref "H1") (pin "1.29") (pinfunction "1.29_1.29") (pintype "bidirectional"))
    )
    (net (code "117") (name "unconnected-(H1-Pad1.30)") (class "Default")
      (node (ref "H1") (pin "1.30") (pinfunction "1.30_1.30") (pintype "bidirectional"))
    )
    (net (code "118") (name "unconnected-(H1-Pad1.31)") (class "Default")
      (node (ref "H1") (pin "1.31") (pinfunction "1.31_1.31") (pintype "bidirectional"))
    )
    (net (code "119") (name "unconnected-(H1-Pad1.32)") (class "Default")
      (node (ref "H1") (pin "1.32") (pinfunction "1.32_1.32") (pintype "bidirectional"))
    )
    (net (code "120") (name "unconnected-(H1-Pad1.33)") (class "Default")
      (node (ref "H1") (pin "1.33") (pinfunction "1.33_1.33") (pintype "bidirectional"))
    )
    (net (code "121") (name "unconnected-(H1-Pad1.34)") (class "Default")
      (node (ref "H1") (pin "1.34") (pinfunction "1.34_1.34") (pintype "bidirectional"))
    )
    (net (code "122") (name "unconnected-(H1-Pad1.35)") (class "Default")
      (node (ref "H1") (pin "1.35") (pinfunction "1.35_1.35") (pintype "bidirectional"))
    )
    (net (code "123") (name "unconnected-(H1-Pad1.36)") (class "Default")
      (node (ref "H1") (pin "1.36") (pinfunction "1.36_1.36") (pintype "bidirectional"))
    )
    (net (code "124") (name "unconnected-(H1-Pad1.37)") (class "Default")
      (node (ref "H1") (pin "1.37") (pinfunction "1.37_1.37") (pintype "bidirectional"))
    )
    (net (code "125") (name "unconnected-(H1-Pad1.38)") (class "Default")
      (node (ref "H1") (pin "1.38") (pinfunction "1.38_1.38") (pintype "bidirectional"))
    )
    (net (code "126") (name "unconnected-(H1-Pad1.39)") (class "Default")
      (node (ref "H1") (pin "1.39") (pinfunction "1.39_1.39") (pintype "bidirectional"))
    )
    (net (code "127") (name "unconnected-(H1-Pad1.40)") (class "Default")
      (node (ref "H1") (pin "1.40") (pinfunction "1.40_1.40") (pintype "bidirectional"))
    )
    (net (code "128") (name "unconnected-(H1-Pad1.41)") (class "Default")
      (node (ref "H1") (pin "1.41") (pinfunction "1.41_1.41") (pintype "bidirectional"))
    )
    (net (code "129") (name "unconnected-(H1-Pad1.42)") (class "Default")
      (node (ref "H1") (pin "1.42") (pinfunction "1.42_1.42") (pintype "bidirectional"))
    )
    (net (code "130") (name "unconnected-(H1-Pad1.43)") (class "Default")
      (node (ref "H1") (pin "1.43") (pinfunction "1.43_1.43") (pintype "bidirectional"))
    )
    (net (code "131") (name "unconnected-(H1-Pad1.44)") (class "Default")
      (node (ref "H1") (pin "1.44") (pinfunction "1.44_1.44") (pintype "bidirectional"))
    )
    (net (code "132") (name "unconnected-(H1-Pad1.45)") (class "Default")
      (node (ref "H1") (pin "1.45") (pinfunction "1.45_1.45") (pintype "bidirectional"))
    )
    (net (code "133") (name "unconnected-(H1-Pad1.46)") (class "Default")
      (node (ref "H1") (pin "1.46") (pinfunction "1.46_1.46") (pintype "bidirectional"))
    )
    (net (code "134") (name "unconnected-(H1-Pad1.47)") (class "Default")
      (node (ref "H1") (pin "1.47") (pinfunction "1.47_1.47") (pintype "bidirectional"))
    )
    (net (code "135") (name "unconnected-(H1-Pad1.48)") (class "Default")
      (node (ref "H1") (pin "1.48") (pinfunction "1.48_1.48") (pintype "bidirectional"))
    )
    (net (code "136") (name "unconnected-(H1-Pad1.49)") (class "Default")
      (node (ref "H1") (pin "1.49") (pinfunction "1.49_1.49") (pintype "bidirectional"))
    )
    (net (code "137") (name "unconnected-(H1-Pad1.50)") (class "Default")
      (node (ref "H1") (pin "1.50") (pinfunction "1.50_1.50") (pintype "bidirectional"))
    )
    (net (code "138") (name "unconnected-(H1-Pad1.51)") (class "Default")
      (node (ref "H1") (pin "1.51") (pinfunction "1.51_1.51") (pintype "bidirectional"))
    )
    (net (code "139") (name "unconnected-(H1-Pad1.52)") (class "Default")
      (node (ref "H1") (pin "1.52") (pinfunction "1.52_1.52") (pintype "bidirectional"))
    )
    (net (code "140") (name "unconnected-(H1-Pad2.1)") (class "Default")
      (node (ref "H1") (pin "2.1") (pinfunction "2.1_2.1") (pintype "bidirectional"))
    )
    (net (code "141") (name "unconnected-(H1-Pad2.2)") (class "Default")
      (node (ref "H1") (pin "2.2") (pinfunction "2.2_2.2") (pintype "bidirectional"))
    )
    (net (code "142") (name "unconnected-(H1-Pad2.3)") (class "Default")
      (node (ref "H1") (pin "2.3") (pinfunction "2.3_2.3") (pintype "bidirectional"))
    )
    (net (code "143") (name "unconnected-(H1-Pad2.4)") (class "Default")
      (node (ref "H1") (pin "2.4") (pinfunction "2.4_2.4") (pintype "bidirectional"))
    )
    (net (code "144") (name "unconnected-(H1-Pad2.5)") (class "Default")
      (node (ref "H1") (pin "2.5") (pinfunction "2.5_2.5") (pintype "bidirectional"))
    )
    (net (code "145") (name "unconnected-(H1-Pad2.6)") (class "Default")
      (node (ref "H1") (pin "2.6") (pinfunction "2.6_2.6") (pintype "bidirectional"))
    )
    (net (code "146") (name "unconnected-(H1-Pad2.8)") (class "Default")
      (node (ref "H1") (pin "2.8") (pinfunction "2.8_2.8") (pintype "bidirectional"))
    )
    (net (code "147") (name "unconnected-(H1-Pad2.9)") (class "Default")
      (node (ref "H1") (pin "2.9") (pinfunction "2.9_2.9") (pintype "bidirectional"))
    )
    (net (code "148") (name "unconnected-(H1-Pad2.10)") (class "Default")
      (node (ref "H1") (pin "2.10") (pinfunction "2.10_2.10") (pintype "bidirectional"))
    )
    (net (code "149") (name "unconnected-(H1-Pad2.11)") (class "Default")
      (node (ref "H1") (pin "2.11") (pinfunction "2.11_2.11") (pintype "bidirectional"))
    )
    (net (code "150") (name "unconnected-(H1-Pad2.12)") (class "Default")
      (node (ref "H1") (pin "2.12") (pinfunction "2.12_2.12") (pintype "bidirectional"))
    )
    (net (code "151") (name "unconnected-(H1-Pad2.15)") (class "Default")
      (node (ref "H1") (pin "2.15") (pinfunction "2.15_2.15") (pintype "bidirectional"))
    )
    (net (code "152") (name "unconnected-(H1-Pad2.16)") (class "Default")
      (node (ref "H1") (pin "2.16") (pinfunction "2.16_2.16") (pintype "bidirectional"))
    )
    (net (code "153") (name "unconnected-(H1-Pad2.18)") (class "Default")
      (node (ref "H1") (pin "2.18") (pinfunction "2.18_2.18") (pintype "bidirectional"))
    )
    (net (code "154") (name "unconnected-(H1-Pad2.19)") (class "Default")
      (node (ref "H1") (pin "2.19") (pinfunction "2.19_2.19") (pintype "bidirectional"))
    )
    (net (code "155") (name "unconnected-(H1-Pad2.20)") (class "Default")
      (node (ref "H1") (pin "2.20") (pinfunction "2.20_2.20") (pintype "bidirectional"))
    )
    (net (code "156") (name "unconnected-(H1-Pad2.23)") (class "Default")
      (node (ref "H1") (pin "2.23") (pinfunction "2.23_2.23") (pintype "bidirectional"))
    )
    (net (code "157") (name "unconnected-(H1-Pad2.24)") (class "Default")
      (node (ref "H1") (pin "2.24") (pinfunction "2.24_2.24") (pintype "bidirectional"))
    )
    (net (code "158") (name "unconnected-(H1-Pad2.31)") (class "Default")
      (node (ref "H1") (pin "2.31") (pinfunction "2.31_2.31") (pintype "bidirectional"))
    )
    (net (code "159") (name "unconnected-(H1-Pad2.33)") (class "Default")
      (node (ref "H1") (pin "2.33") (pinfunction "2.33_2.33") (pintype "bidirectional"))
    )
    (net (code "160") (name "unconnected-(H1-Pad2.34)") (class "Default")
      (node (ref "H1") (pin "2.34") (pinfunction "2.34_2.34") (pintype "bidirectional"))
    )
    (net (code "161") (name "unconnected-(H1-Pad2.35)") (class "Default")
      (node (ref "H1") (pin "2.35") (pinfunction "2.35_2.35") (pintype "bidirectional"))
    )
    (net (code "162") (name "unconnected-(H1-Pad2.36)") (class "Default")
      (node (ref "H1") (pin "2.36") (pinfunction "2.36_2.36") (pintype "bidirectional"))
    )
    (net (code "163") (name "unconnected-(H1-Pad2.37)") (class "Default")
      (node (ref "H1") (pin "2.37") (pinfunction "2.37_2.37") (pintype "bidirectional"))
    )
    (net (code "164") (name "unconnected-(H1-Pad2.38)") (class "Default")
      (node (ref "H1") (pin "2.38") (pinfunction "2.38_2.38") (pintype "bidirectional"))
    )
    (net (code "165") (name "unconnected-(H1-Pad2.39)") (class "Default")
      (node (ref "H1") (pin "2.39") (pinfunction "2.39_2.39") (pintype "bidirectional"))
    )
    (net (code "166") (name "unconnected-(H1-Pad2.40)") (class "Default")
      (node (ref "H1") (pin "2.40") (pinfunction "2.40_2.40") (pintype "bidirectional"))
    )
    (net (code "167") (name "unconnected-(H1-Pad2.41)") (class "Default")
      (node (ref "H1") (pin "2.41") (pinfunction "2.41_2.41") (pintype "bidirectional"))
    )
    (net (code "168") (name "unconnected-(H1-Pad2.42)") (class "Default")
      (node (ref "H1") (pin "2.42") (pinfunction "2.42_2.42") (pintype "bidirectional"))
    )
    (net (code "169") (name "unconnected-(H1-Pad2.43)") (class "Default")
      (node (ref "H1") (pin "2.43") (pinfunction "2.43_2.43") (pintype "bidirectional"))
    )
    (net (code "170") (name "unconnected-(H1-Pad2.44)") (class "Default")
      (node (ref "H1") (pin "2.44") (pinfunction "2.44_2.44") (pintype "bidirectional"))
    )
    (net (code "171") (name "unconnected-(H1-Pad2.45)") (class "Default")
      (node (ref "H1") (pin "2.45") (pinfunction "2.45_2.45") (pintype "bidirectional"))
    )
    (net (code "172") (name "unconnected-(H1-Pad2.46)") (class "Default")
      (node (ref "H1") (pin "2.46") (pinfunction "2.46_2.46") (pintype "bidirectional"))
    )
    (net (code "173") (name "unconnected-(H1-Pad2.49)") (class "Default")
      (node (ref "H1") (pin "2.49") (pinfunction "2.49_2.49") (pintype "bidirectional"))
    )
    (net (code "174") (name "unconnected-(H1-Pad2.50)") (class "Default")
      (node (ref "H1") (pin "2.50") (pinfunction "2.50_2.50") (pintype "bidirectional"))
    )
    (net (code "175") (name "unconnected-(H1-Pad2.51)") (class "Default")
      (node (ref "H1") (pin "2.51") (pinfunction "2.51_2.51") (pintype "bidirectional"))
    )
    (net (code "176") (name "unconnected-(H1-Pad2.52)") (class "Default")
      (node (ref "H1") (pin "2.52") (pinfunction "2.52_2.52") (pintype "bidirectional"))
    )
    (net (code "177") (name "unconnected-(H1-PadP$1)") (class "Default")
      (node (ref "H1") (pin "P$1") (pinfunction "P$1_P$1") (pintype "bidirectional"))
    )
    (net (code "178") (name "unconnected-(H1-PadP$2)") (class "Default")
      (node (ref "H1") (pin "P$2") (pinfunction "P$2_P$2") (pintype "bidirectional"))
    )
    (net (code "179") (name "unconnected-(H1-PadP$3)") (class "Default")
      (node (ref "H1") (pin "P$3") (pinfunction "P$3_P$3") (pintype "bidirectional"))
    )
    (net (code "180") (name "unconnected-(JP4-Pad1)") (class "Default")
      (node (ref "JP4") (pin "1") (pinfunction "1_1") (pintype "passive"))
    )
    (net (code "181") (name "unconnected-(P8AB-1-Pad34)") (class "Default")
      (node (ref "P8") (pin "34") (pinfunction "1_34") (pintype "passive"))
    )
    (net (code "182") (name "unconnected-(P8AS-1-Pad8)") (class "Default")
      (node (ref "P8") (pin "8") (pinfunction "1_8") (pintype "passive"))
    )
    (net (code "183") (name "unconnected-(P8AT-1-Pad9)") (class "Default")
      (node (ref "P8") (pin "9") (pinfunction "1_9") (pintype "passive"))
    )
    (net (code "184") (name "unconnected-(P8B-1-Pad10)") (class "Default")
      (node (ref "P8") (pin "10") (pinfunction "1_10") (pintype "passive"))
    )
    (net (code "185") (name "unconnected-(P8E-1-Pad13)") (class "Default")
      (node (ref "P8") (pin "13") (pinfunction "1_13") (pintype "passive"))
    )
    (net (code "186") (name "unconnected-(P8F-1-Pad14)") (class "Default")
      (node (ref "P8") (pin "14") (pinfunction "1_14") (pintype "passive"))
    )
    (net (code "187") (name "unconnected-(P8K-1-Pad19)") (class "Default")
      (node (ref "P8") (pin "19") (pinfunction "1_19") (pintype "passive"))
    )
    (net (code "188") (name "unconnected-(P8O-1-Pad22)") (class "Default")
      (node (ref "P8") (pin "22") (pinfunction "1_22") (pintype "passive"))
    )
    (net (code "189") (name "unconnected-(P9AJ-1-Pad41)") (class "Default")
      (node (ref "P9") (pin "41") (pinfunction "1_41") (pintype "passive"))
    )
    (net (code "190") (name "unconnected-(P9AL-1-Pad43)") (class "Default")
      (node (ref "P9") (pin "43") (pinfunction "1_43") (pintype "passive"))
    )
    (net (code "191") (name "unconnected-(P9AM-1-Pad44)") (class "Default")
      (node (ref "P9") (pin "44") (pinfunction "1_44") (pintype "passive"))
    )
    (net (code "192") (name "unconnected-(P9AN-1-Pad45)") (class "Default")
      (node (ref "P9") (pin "45") (pinfunction "1_45") (pintype "passive"))
    )
    (net (code "193") (name "unconnected-(P9AO-1-Pad46)") (class "Default")
      (node (ref "P9") (pin "46") (pinfunction "1_46") (pintype "passive"))
    )
    (net (code "194") (name "unconnected-(P9AR-1-Pad7)") (class "Default")
      (node (ref "P9") (pin "7") (pinfunction "1_7") (pintype "passive"))
    )
    (net (code "195") (name "unconnected-(P9AS-1-Pad8)") (class "Default")
      (node (ref "P9") (pin "8") (pinfunction "1_8") (pintype "passive"))
    )
    (net (code "196") (name "unconnected-(P9AT-1-Pad9)") (class "Default")
      (node (ref "P9") (pin "9") (pinfunction "1_9") (pintype "passive"))
    )
    (net (code "197") (name "unconnected-(P9F-1-Pad14)") (class "Default")
      (node (ref "P9") (pin "14") (pinfunction "1_14") (pintype "passive"))
    )
    (net (code "198") (name "unconnected-(P9H-1-Pad16)") (class "Default")
      (node (ref "P9") (pin "16") (pinfunction "1_16") (pintype "passive"))
    )
    (net (code "199") (name "unconnected-(P9I-1-Pad17)") (class "Default")
      (node (ref "P9") (pin "17") (pinfunction "1_17") (pintype "passive"))
    )
    (net (code "200") (name "unconnected-(P9J-1-Pad18)") (class "Default")
      (node (ref "P9") (pin "18") (pinfunction "1_18") (pintype "passive"))
    )
    (net (code "201") (name "unconnected-(P9Z-1-Pad32)") (class "Default")
      (node (ref "P9") (pin "32") (pinfunction "1_32") (pintype "passive"))
    )
    (net (code "202") (name "unconnected-(U1-NC-Pad7)") (class "Default")
      (node (ref "U1") (pin "7") (pinfunction "NC_7") (pintype "no_connect"))
    )
    (net (code "203") (name "unconnected-(U1-NC_2-Pad2)") (class "Default")
      (node (ref "U1") (pin "2") (pinfunction "NC_2_2") (pintype "no_connect"))
    )
    (net (code "204") (name "unconnected-(U1-NC_3-Pad3)") (class "Default")
      (node (ref "U1") (pin "3") (pinfunction "NC_3_3") (pintype "no_connect"))
    )
    (net (code "205") (name "unconnected-(U1-NC_4-Pad6)") (class "Default")
      (node (ref "U1") (pin "6") (pinfunction "NC_4_6") (pintype "no_connect"))
    )
    (net (code "206") (name "unconnected-(U3-DIO0-Pad10)") (class "Default")
      (node (ref "U3") (pin "10") (pinfunction "DIO0_10") (pintype "bidirectional"))
    )
    (net (code "207") (name "unconnected-(U3-DIO1-Pad11)") (class "Default")
      (node (ref "U3") (pin "11") (pinfunction "DIO1_11") (pintype "bidirectional"))
    )
    (net (code "208") (name "unconnected-(U3-DIO2-Pad12)") (class "Default")
      (node (ref "U3") (pin "12") (pinfunction "DIO2_12") (pintype "bidirectional"))
    )
    (net (code "209") (name "unconnected-(U3-DIO3-Pad13)") (class "Default")
      (node (ref "U3") (pin "13") (pinfunction "DIO3_13") (pintype "bidirectional"))
    )
    (net (code "210") (name "unconnected-(U3-DIO4-Pad14)") (class "Default")
      (node (ref "U3") (pin "14") (pinfunction "DIO4_14") (pintype "bidirectional"))
    )
    (net (code "211") (name "unconnected-(U3-DIO5-Pad15)") (class "Default")
      (node (ref "U3") (pin "15") (pinfunction "DIO5_15") (pintype "bidirectional"))
    )
    (net (code "212") (name "unconnected-(U3-NC-Pad1)") (class "Default")
      (node (ref "U3") (pin "1") (pinfunction "NC_1") (pintype "bidirectional"))
    )
    (net (code "213") (name "unconnected-(U6-P$3-Pad3)") (class "Default")
      (node (ref "U6") (pin "3") (pinfunction "P$3_3") (pintype "bidirectional"))
    )
    (net (code "214") (name "unconnected-(U6-P$4-Pad4)") (class "Default")
      (node (ref "U6") (pin "4") (pinfunction "P$4_4") (pintype "bidirectional"))
    )
    (net (code "215") (name "unconnected-(U6-P$5-Pad5)") (class "Default")
      (node (ref "U6") (pin "5") (pinfunction "P$5_5") (pintype "bidirectional"))
    )
    (net (code "216") (name "unconnected-(U6-P$6-Pad6)") (class "Default")
      (node (ref "U6") (pin "6") (pinfunction "P$6_6") (pintype "bidirectional"))
    )
    (net (code "217") (name "unconnected-(U6-P$8-Pad8)") (class "Default")
      (node (ref "U6") (pin "8") (pinfunction "P$8_8") (pintype "bidirectional"))
    )
    (net (code "218") (name "unconnected-(U6-P$10-Pad10)") (class "Default")
      (node (ref "U6") (pin "10") (pinfunction "P$10_10") (pintype "bidirectional"))
    )
    (net (code "219") (name "unconnected-(U6-P$12-Pad12)") (class "Default")
      (node (ref "U6") (pin "12") (pinfunction "P$12_12") (pintype "bidirectional"))
    )
    (net (code "220") (name "unconnected-(U6-P$13-Pad13)") (class "Default")
      (node (ref "U6") (pin "13") (pinfunction "P$13_13") (pintype "bidirectional"))
    )
    (net (code "221") (name "unconnected-(U6-P$14-Pad14)") (class "Default")
      (node (ref "U6") (pin "14") (pinfunction "P$14_14") (pintype "bidirectional"))
    )
    (net (code "222") (name "unconnected-(U6-P$15-Pad15)") (class "Default")
      (node (ref "U6") (pin "15") (pinfunction "P$15_15") (pintype "bidirectional"))
    )
    (net (code "223") (name "unconnected-(U6-P$16-Pad16)") (class "Default")
      (node (ref "U6") (pin "16") (pinfunction "P$16_16") (pintype "bidirectional"))
    )
    (net (code "224") (name "unconnected-(U6-P$17-Pad17)") (class "Default")
      (node (ref "U6") (pin "17") (pinfunction "P$17_17") (pintype "bidirectional"))
    )
    (net (code "225") (name "unconnected-(U6-P$19-Pad19)") (class "Default")
      (node (ref "U6") (pin "19") (pinfunction "P$19_19") (pintype "bidirectional"))
    )
    (net (code "226") (name "unconnected-(U6-P$20-Pad20)") (class "Default")
      (node (ref "U6") (pin "20") (pinfunction "P$20_20") (pintype "bidirectional"))
    )
    (net (code "227") (name "unconnected-(U6-P$22-Pad22)") (class "Default")
      (node (ref "U6") (pin "22") (pinfunction "P$22_22") (pintype "bidirectional"))
    )
    (net (code "228") (name "unconnected-(U6-P$23-Pad23)") (class "Default")
      (node (ref "U6") (pin "23") (pinfunction "P$23_23") (pintype "bidirectional"))
    )
    (net (code "229") (name "unconnected-(U6-P$24-Pad24)") (class "Default")
      (node (ref "U6") (pin "24") (pinfunction "P$24_24") (pintype "bidirectional"))
    )
    (net (code "230") (name "unconnected-(U6-P$25-Pad25)") (class "Default")
      (node (ref "U6") (pin "25") (pinfunction "P$25_25") (pintype "bidirectional"))
    )
    (net (code "231") (name "unconnected-(U6-P$26-Pad26)") (class "Default")
      (node (ref "U6") (pin "26") (pinfunction "P$26_26") (pintype "bidirectional"))
    )
    (net (code "232") (name "unconnected-(U6-P$27-Pad27)") (class "Default")
      (node (ref "U6") (pin "27") (pinfunction "P$27_27") (pintype "bidirectional"))
    )
    (net (code "233") (name "unconnected-(U6-P$28-Pad28)") (class "Default")
      (node (ref "U6") (pin "28") (pinfunction "P$28_28") (pintype "bidirectional"))
    )
    (net (code "234") (name "unconnected-(U6-P$29-Pad29)") (class "Default")
      (node (ref "U6") (pin "29") (pinfunction "P$29_29") (pintype "bidirectional"))
    )
    (net (code "235") (name "unconnected-(U6-P$30-Pad30)") (class "Default")
      (node (ref "U6") (pin "30") (pinfunction "P$30_30") (pintype "bidirectional"))
    )
    (net (code "236") (name "unconnected-(U6-P$31-Pad31)") (class "Default")
      (node (ref "U6") (pin "31") (pinfunction "P$31_31") (pintype "bidirectional"))
    )
    (net (code "237") (name "unconnected-(U6-P$33-Pad33)") (class "Default")
      (node (ref "U6") (pin "33") (pinfunction "P$33_33") (pintype "bidirectional"))
    )
    (net (code "238") (name "unconnected-(U6-P$34-Pad34)") (class "Default")
      (node (ref "U6") (pin "34") (pinfunction "P$34_34") (pintype "bidirectional"))
    )
    (net (code "239") (name "unconnected-(U6-P$35-Pad35)") (class "Default")
      (node (ref "U6") (pin "35") (pinfunction "P$35_35") (pintype "bidirectional"))
    )
    (net (code "240") (name "unconnected-(U6-P$36-Pad36)") (class "Default")
      (node (ref "U6") (pin "36") (pinfunction "P$36_36") (pintype "bidirectional"))
    )
    (net (code "241") (name "unconnected-(U6-P$37-Pad37)") (class "Default")
      (node (ref "U6") (pin "37") (pinfunction "P$37_37") (pintype "bidirectional"))
    )
    (net (code "242") (name "unconnected-(U6-P$38-Pad38)") (class "Default")
      (node (ref "U6") (pin "38") (pinfunction "P$38_38") (pintype "bidirectional"))
    )
    (net (code "243") (name "unconnected-(U6-P$39-Pad39)") (class "Default")
      (node (ref "U6") (pin "39") (pinfunction "P$39_39") (pintype "bidirectional"))
    )
    (net (code "244") (name "unconnected-(U6-P$40-Pad40)") (class "Default")
      (node (ref "U6") (pin "40") (pinfunction "P$40_40") (pintype "bidirectional"))
    )
    (net (code "245") (name "unconnected-(U6-P$41-Pad41)") (class "Default")
      (node (ref "U6") (pin "41") (pinfunction "P$41_41") (pintype "bidirectional"))
    )
    (net (code "246") (name "unconnected-(U6-P$43-Pad43)") (class "Default")
      (node (ref "U6") (pin "43") (pinfunction "P$43_43") (pintype "bidirectional"))
    )
    (net (code "247") (name "unconnected-(U6-P$45-Pad45)") (class "Default")
      (node (ref "U6") (pin "45") (pinfunction "P$45_45") (pintype "bidirectional"))
    )
    (net (code "248") (name "unconnected-(U6-P$46-Pad46)") (class "Default")
      (node (ref "U6") (pin "46") (pinfunction "P$46_46") (pintype "bidirectional"))
    )
    (net (code "249") (name "unconnected-(U6-P$47-Pad47)") (class "Default")
      (node (ref "U6") (pin "47") (pinfunction "P$47_47") (pintype "bidirectional"))
    )
    (net (code "250") (name "unconnected-(U6-P$48-Pad48)") (class "Default")
      (node (ref "U6") (pin "48") (pinfunction "P$48_48") (pintype "bidirectional"))
    )
    (net (code "251") (name "unconnected-(U6-P$49-Pad49)") (class "Default")
      (node (ref "U6") (pin "49") (pinfunction "P$49_49") (pintype "bidirectional"))
    )
    (net (code "252") (name "unconnected-(U6-P$50-Pad50)") (class "Default")
      (node (ref "U6") (pin "50") (pinfunction "P$50_50") (pintype "bidirectional"))
    )
    (net (code "253") (name "unconnected-(U6-P$51-Pad51)") (class "Default")
      (node (ref "U6") (pin "51") (pinfunction "P$51_51") (pintype "bidirectional"))
    )
    (net (code "254") (name "unconnected-(U6-P$52-Pad52)") (class "Default")
      (node (ref "U6") (pin "52") (pinfunction "P$52_52") (pintype "bidirectional"))
    )
    (net (code "255") (name "unconnected-(U6-P$53-Pad53)") (class "Default")
      (node (ref "U6") (pin "53") (pinfunction "P$53_53") (pintype "bidirectional"))
    )
    (net (code "256") (name "unconnected-(U6-P$54-Pad54)") (class "Default")
      (node (ref "U6") (pin "54") (pinfunction "P$54_54") (pintype "bidirectional"))
    )
    (net (code "257") (name "unconnected-(U6-P$55-Pad55)") (class "Default")
      (node (ref "U6") (pin "55") (pinfunction "P$55_55") (pintype "bidirectional"))
    )
    (net (code "258") (name "unconnected-(U6-P$56-Pad56)") (class "Default")
      (node (ref "U6") (pin "56") (pinfunction "P$56_56") (pintype "bidirectional"))
    )
    (net (code "259") (name "unconnected-(U6-P$57-Pad57)") (class "Default")
      (node (ref "U6") (pin "57") (pinfunction "P$57_57") (pintype "bidirectional"))
    )
    (net (code "260") (name "unconnected-(U6-P$58-Pad58)") (class "Default")
      (node (ref "U6") (pin "58") (pinfunction "P$58_58") (pintype "bidirectional"))
    )
    (net (code "261") (name "unconnected-(U6-P$59-Pad59)") (class "Default")
      (node (ref "U6") (pin "59") (pinfunction "P$59_59") (pintype "bidirectional"))
    )
    (net (code "262") (name "unconnected-(U6-P$60-Pad60)") (class "Default")
      (node (ref "U6") (pin "60") (pinfunction "P$60_60") (pintype "bidirectional"))
    )
    (net (code "263") (name "unconnected-(U6-P$61-Pad61)") (class "Default")
      (node (ref "U6") (pin "61") (pinfunction "P$61_61") (pintype "bidirectional"))
    )
    (net (code "264") (name "unconnected-(U6-P$62-Pad62)") (class "Default")
      (node (ref "U6") (pin "62") (pinfunction "P$62_62") (pintype "bidirectional"))
    )
    (net (code "265") (name "unconnected-(U6-P$63-Pad63)") (class "Default")
      (node (ref "U6") (pin "63") (pinfunction "P$63_63") (pintype "bidirectional"))
    )
    (net (code "266") (name "unconnected-(U6-P$65-Pad65)") (class "Default")
      (node (ref "U6") (pin "65") (pinfunction "P$65_65") (pintype "bidirectional"))
    )
    (net (code "267") (name "unconnected-(U6-P$66-Pad66)") (class "Default")
      (node (ref "U6") (pin "66") (pinfunction "P$66_66") (pintype "bidirectional"))
    )
    (net (code "268") (name "unconnected-(U6-P$67-Pad67)") (class "Default")
      (node (ref "U6") (pin "67") (pinfunction "P$67_67") (pintype "bidirectional"))
    )
    (net (code "269") (name "unconnected-(U6-P$68-Pad68)") (class "Default")
      (node (ref "U6") (pin "68") (pinfunction "P$68_68") (pintype "bidirectional"))
    )
    (net (code "270") (name "unconnected-(U6-P$69-Pad69)") (class "Default")
      (node (ref "U6") (pin "69") (pinfunction "P$69_69") (pintype "bidirectional"))
    )
    (net (code "271") (name "unconnected-(U7-PPS-Pad2)") (class "Default")
      (node (ref "U7") (pin "2") (pinfunction "PPS_2") (pintype "bidirectional"))
    )
    (net (code "272") (name "unconnected-(X1-P$1-Pad1)") (class "Default")
      (node (ref "X1") (pin "1") (pinfunction "P$1_1") (pintype "bidirectional"))
    )
    (net (code "273") (name "unconnected-(X1-P$4-Pad4)") (class "Default")
      (node (ref "X1") (pin "4") (pinfunction "P$4_4") (pintype "bidirectional"))
    )
    (net (code "274") (name "unconnected-(X1-P$6-Pad6)") (class "Default")
      (node (ref "X1") (pin "6") (pinfunction "P$6_6") (pintype "bidirectional"))
    )
    (net (code "275") (name "unconnected-(X1-P$7-Pad7)") (class "Default")
      (node (ref "X1") (pin "7") (pinfunction "P$7_7") (pintype "bidirectional"))
    )
    (net (code "276") (name "unconnected-(X1-P$9-Pad9)") (class "Default")
      (node (ref "X1") (pin "9") (pinfunction "P$9_9") (pintype "bidirectional"))
    )
    (net (code "277") (name "unconnected-(X1-P$12-Pad12)") (class "Default")
      (node (ref "X1") (pin "12") (pinfunction "P$12_12") (pintype "bidirectional"))
    )
    (net (code "278") (name "unconnected-(X1-P$14-Pad14)") (class "Default")
      (node (ref "X1") (pin "14") (pinfunction "P$14_14") (pintype "bidirectional"))
    )
    (net (code "279") (name "unconnected-(X1-P$17-Pad17)") (class "Default")
      (node (ref "X1") (pin "17") (pinfunction "P$17_17") (pintype "bidirectional"))
    )
    (net (code "280") (name "unconnected-(X1-P$20-Pad20)") (class "Default")
      (node (ref "X1") (pin "20") (pinfunction "P$20_20") (pintype "bidirectional"))
    )
    (net (code "281") (name "unconnected-(X1-P$25-Pad25)") (class "Default")
      (node (ref "X1") (pin "25") (pinfunction "P$25_25") (pintype "bidirectional"))
    )
    (net (code "282") (name "unconnected-(X1-P$27-Pad27)") (class "Default")
      (node (ref "X1") (pin "27") (pinfunction "P$27_27") (pintype "bidirectional"))
    )
    (net (code "283") (name "unconnected-(X1-P$28-Pad28)") (class "Default")
      (node (ref "X1") (pin "28") (pinfunction "P$28_28") (pintype "bidirectional"))
    )
    (net (code "284") (name "unconnected-(X1-P$29-Pad29)") (class "Default")
      (node (ref "X1") (pin "29") (pinfunction "P$29_29") (pintype "bidirectional"))
    )
    (net (code "285") (name "unconnected-(X1-P$30-Pad30)") (class "Default")
      (node (ref "X1") (pin "30") (pinfunction "P$30_30") (pintype "bidirectional"))
    )
    (net (code "286") (name "unconnected-(X1-P$31-Pad31)") (class "Default")
      (node (ref "X1") (pin "31") (pinfunction "P$31_31") (pintype "bidirectional"))
    )
    (net (code "287") (name "unconnected-(X1-P$32-Pad32)") (class "Default")
      (node (ref "X1") (pin "32") (pinfunction "P$32_32") (pintype "bidirectional"))
    )
    (net (code "288") (name "unconnected-(X1-P$33-Pad33)") (class "Default")
      (node (ref "X1") (pin "33") (pinfunction "P$33_33") (pintype "bidirectional"))
    )
    (net (code "289") (name "unconnected-(X1-P$34-Pad34)") (class "Default")
      (node (ref "X1") (pin "34") (pinfunction "P$34_34") (pintype "bidirectional"))
    )
    (net (code "290") (name "unconnected-(X1-P$35-Pad35)") (class "Default")
      (node (ref "X1") (pin "35") (pinfunction "P$35_35") (pintype "bidirectional"))
    )
    (net (code "291") (name "unconnected-(X1-P$36-Pad36)") (class "Default")
      (node (ref "X1") (pin "36") (pinfunction "P$36_36") (pintype "bidirectional"))
    )
    (net (code "292") (name "unconnected-(X1-P$37-Pad37)") (class "Default")
      (node (ref "X1") (pin "37") (pinfunction "P$37_37") (pintype "bidirectional"))
    )
    (net (code "293") (name "unconnected-(X1-P$38-Pad38)") (class "Default")
      (node (ref "X1") (pin "38") (pinfunction "P$38_38") (pintype "bidirectional"))
    )
    (net (code "294") (name "unconnected-(X1-P$40-Pad40)") (class "Default")
      (node (ref "X1") (pin "40") (pinfunction "P$40_40") (pintype "bidirectional"))
    )
    (net (code "295") (name "unconnected-(X2-Pad1)") (class "Default")
      (node (ref "X2") (pin "1") (pinfunction "1_1") (pintype "passive"))
    )
    (net (code "296") (name "unconnected-(X2AA-1-Pad33)") (class "Default")
      (node (ref "X2") (pin "33") (pinfunction "1_33") (pintype "passive"))
    )
    (net (code "297") (name "unconnected-(X2AB-1-Pad34)") (class "Default")
      (node (ref "X2") (pin "34") (pinfunction "1_34") (pintype "passive"))
    )
    (net (code "298") (name "unconnected-(X2AC-1-Pad35)") (class "Default")
      (node (ref "X2") (pin "35") (pinfunction "1_35") (pintype "passive"))
    )
    (net (code "299") (name "unconnected-(X2AD-1-Pad36)") (class "Default")
      (node (ref "X2") (pin "36") (pinfunction "1_36") (pintype "passive"))
    )
    (net (code "300") (name "unconnected-(X2AE-1-Pad37)") (class "Default")
      (node (ref "X2") (pin "37") (pinfunction "1_37") (pintype "passive"))
    )
    (net (code "301") (name "unconnected-(X2AF-1-Pad38)") (class "Default")
      (node (ref "X2") (pin "38") (pinfunction "1_38") (pintype "passive"))
    )
    (net (code "302") (name "unconnected-(X2AG-1-Pad39)") (class "Default")
      (node (ref "X2") (pin "39") (pinfunction "1_39") (pintype "passive"))
    )
    (net (code "303") (name "unconnected-(X2AH-1-Pad4)") (class "Default")
      (node (ref "X2") (pin "4") (pinfunction "1_4") (pintype "passive"))
    )
    (net (code "304") (name "unconnected-(X2AI-1-Pad40)") (class "Default")
      (node (ref "X2") (pin "40") (pinfunction "1_40") (pintype "passive"))
    )
    (net (code "305") (name "unconnected-(X2AJ-1-Pad5)") (class "Default")
      (node (ref "X2") (pin "5") (pinfunction "1_5") (pintype "passive"))
    )
    (net (code "306") (name "unconnected-(X2AK-1-Pad6)") (class "Default")
      (node (ref "X2") (pin "6") (pinfunction "1_6") (pintype "passive"))
    )
    (net (code "307") (name "unconnected-(X2AL-1-Pad7)") (class "Default")
      (node (ref "X2") (pin "7") (pinfunction "1_7") (pintype "passive"))
    )
    (net (code "308") (name "unconnected-(X2AM-1-Pad8)") (class "Default")
      (node (ref "X2") (pin "8") (pinfunction "1_8") (pintype "passive"))
    )
    (net (code "309") (name "unconnected-(X2AN-1-Pad9)") (class "Default")
      (node (ref "X2") (pin "9") (pinfunction "1_9") (pintype "passive"))
    )
    (net (code "310") (name "unconnected-(X2B-1-Pad10)") (class "Default")
      (node (ref "X2") (pin "10") (pinfunction "1_10") (pintype "passive"))
    )
    (net (code "311") (name "unconnected-(X2C-1-Pad11)") (class "Default")
      (node (ref "X2") (pin "11") (pinfunction "1_11") (pintype "passive"))
    )
    (net (code "312") (name "unconnected-(X2D-1-Pad12)") (class "Default")
      (node (ref "X2") (pin "12") (pinfunction "1_12") (pintype "passive"))
    )
    (net (code "313") (name "unconnected-(X2E-1-Pad13)") (class "Default")
      (node (ref "X2") (pin "13") (pinfunction "1_13") (pintype "passive"))
    )
    (net (code "314") (name "unconnected-(X2F-1-Pad14)") (class "Default")
      (node (ref "X2") (pin "14") (pinfunction "1_14") (pintype "passive"))
    )
    (net (code "315") (name "unconnected-(X2G-1-Pad15)") (class "Default")
      (node (ref "X2") (pin "15") (pinfunction "1_15") (pintype "passive"))
    )
    (net (code "316") (name "unconnected-(X2H-1-Pad16)") (class "Default")
      (node (ref "X2") (pin "16") (pinfunction "1_16") (pintype "passive"))
    )
    (net (code "317") (name "unconnected-(X2I-1-Pad17)") (class "Default")
      (node (ref "X2") (pin "17") (pinfunction "1_17") (pintype "passive"))
    )
    (net (code "318") (name "unconnected-(X2J-1-Pad18)") (class "Default")
      (node (ref "X2") (pin "18") (pinfunction "1_18") (pintype "passive"))
    )
    (net (code "319") (name "unconnected-(X2K-1-Pad19)") (class "Default")
      (node (ref "X2") (pin "19") (pinfunction "1_19") (pintype "passive"))
    )
    (net (code "320") (name "unconnected-(X2L-1-Pad2)") (class "Default")
      (node (ref "X2") (pin "2") (pinfunction "1_2") (pintype "passive"))
    )
    (net (code "321") (name "unconnected-(X2M-1-Pad20)") (class "Default")
      (node (ref "X2") (pin "20") (pinfunction "1_20") (pintype "passive"))
    )
    (net (code "322") (name "unconnected-(X2N-1-Pad21)") (class "Default")
      (node (ref "X2") (pin "21") (pinfunction "1_21") (pintype "passive"))
    )
    (net (code "323") (name "unconnected-(X2O-1-Pad22)") (class "Default")
      (node (ref "X2") (pin "22") (pinfunction "1_22") (pintype "passive"))
    )
    (net (code "324") (name "unconnected-(X2P-1-Pad23)") (class "Default")
      (node (ref "X2") (pin "23") (pinfunction "1_23") (pintype "passive"))
    )
    (net (code "325") (name "unconnected-(X2Q-1-Pad24)") (class "Default")
      (node (ref "X2") (pin "24") (pinfunction "1_24") (pintype "passive"))
    )
    (net (code "326") (name "unconnected-(X2R-1-Pad25)") (class "Default")
      (node (ref "X2") (pin "25") (pinfunction "1_25") (pintype "passive"))
    )
    (net (code "327") (name "unconnected-(X2S-1-Pad26)") (class "Default")
      (node (ref "X2") (pin "26") (pinfunction "1_26") (pintype "passive"))
    )
    (net (code "328") (name "unconnected-(X2T-1-Pad27)") (class "Default")
      (node (ref "X2") (pin "27") (pinfunction "1_27") (pintype "passive"))
    )
    (net (code "329") (name "unconnected-(X2U-1-Pad28)") (class "Default")
      (node (ref "X2") (pin "28") (pinfunction "1_28") (pintype "passive"))
    )
    (net (code "330") (name "unconnected-(X2V-1-Pad29)") (class "Default")
      (node (ref "X2") (pin "29") (pinfunction "1_29") (pintype "passive"))
    )
    (net (code "331") (name "unconnected-(X2W-1-Pad3)") (class "Default")
      (node (ref "X2") (pin "3") (pinfunction "1_3") (pintype "passive"))
    )
    (net (code "332") (name "unconnected-(X2X-1-Pad30)") (class "Default")
      (node (ref "X2") (pin "30") (pinfunction "1_30") (pintype "passive"))
    )
    (net (code "333") (name "unconnected-(X2Y-1-Pad31)") (class "Default")
      (node (ref "X2") (pin "31") (pinfunction "1_31") (pintype "passive"))
    )
    (net (code "334") (name "unconnected-(X2Z-1-Pad32)") (class "Default")
      (node (ref "X2") (pin "32") (pinfunction "1_32") (pintype "passive"))
    )
  )
)
